# 20160428.net
KiCad netlist of a schematic drawn in Altium Designer
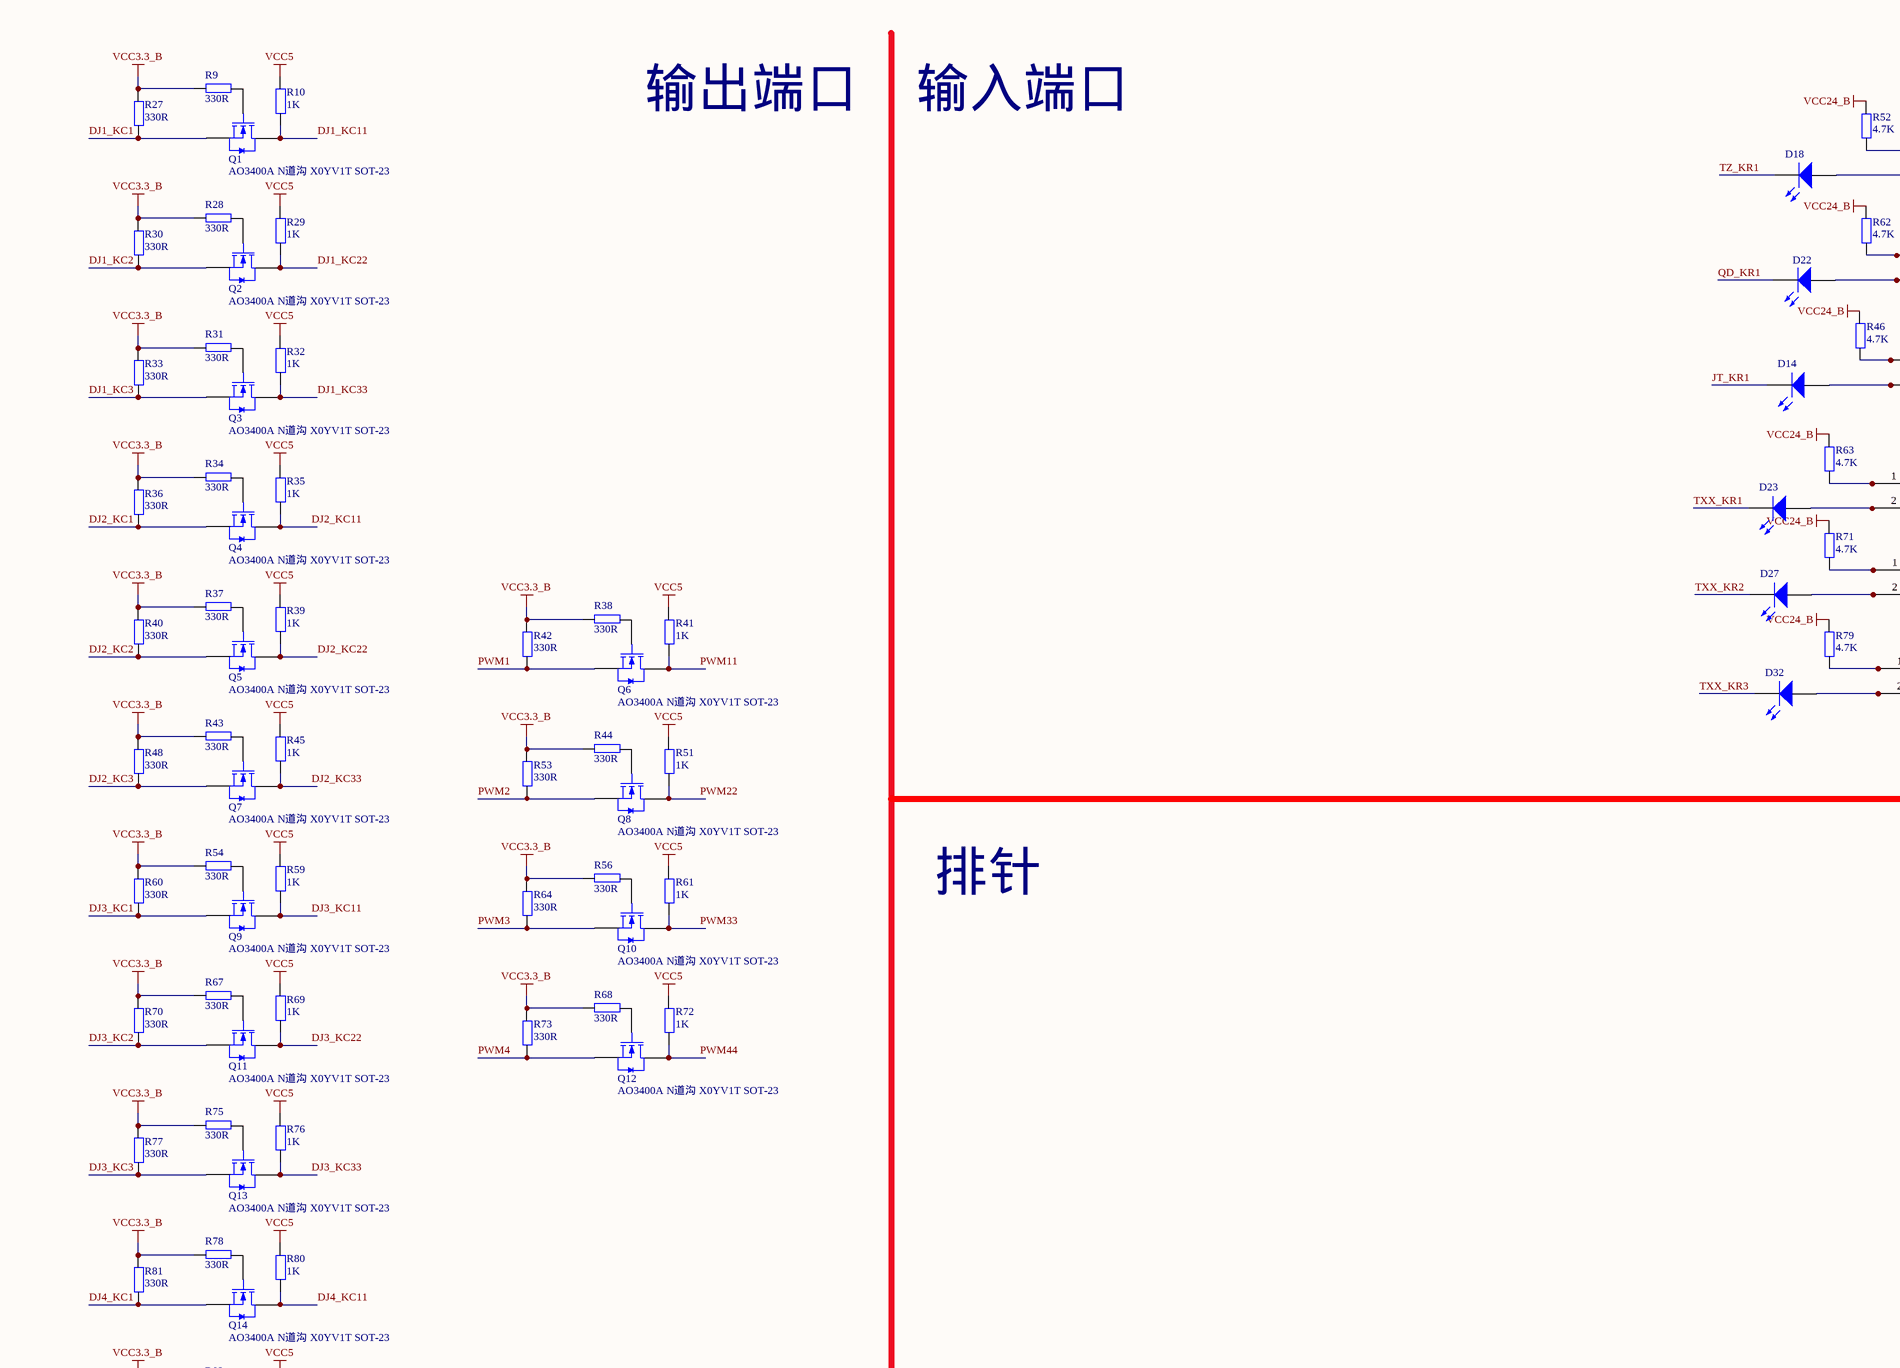
[diagram p0: 底板20160428.SchDoc, top left]
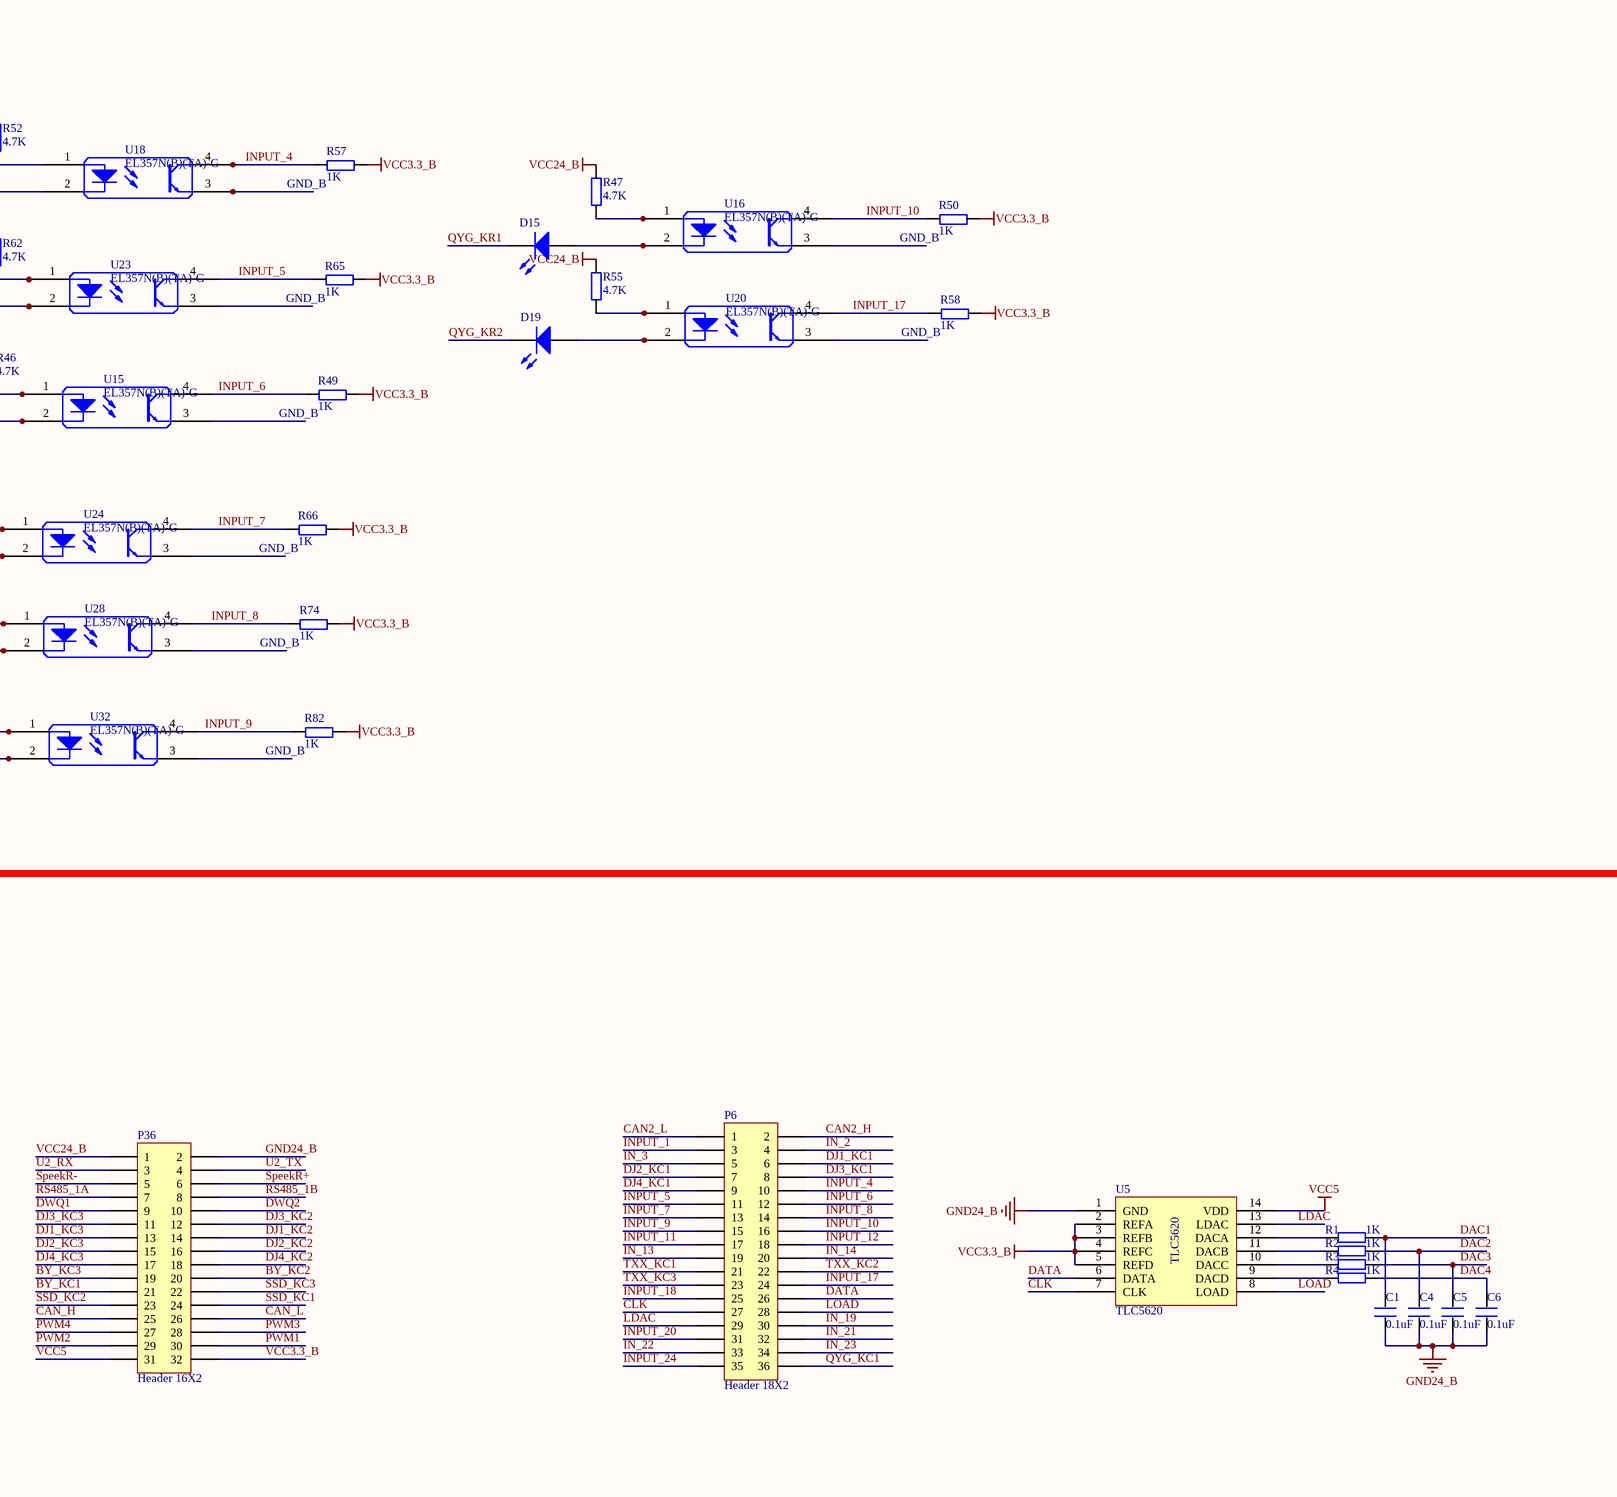
[diagram p1: 底板20160428.SchDoc, top right]
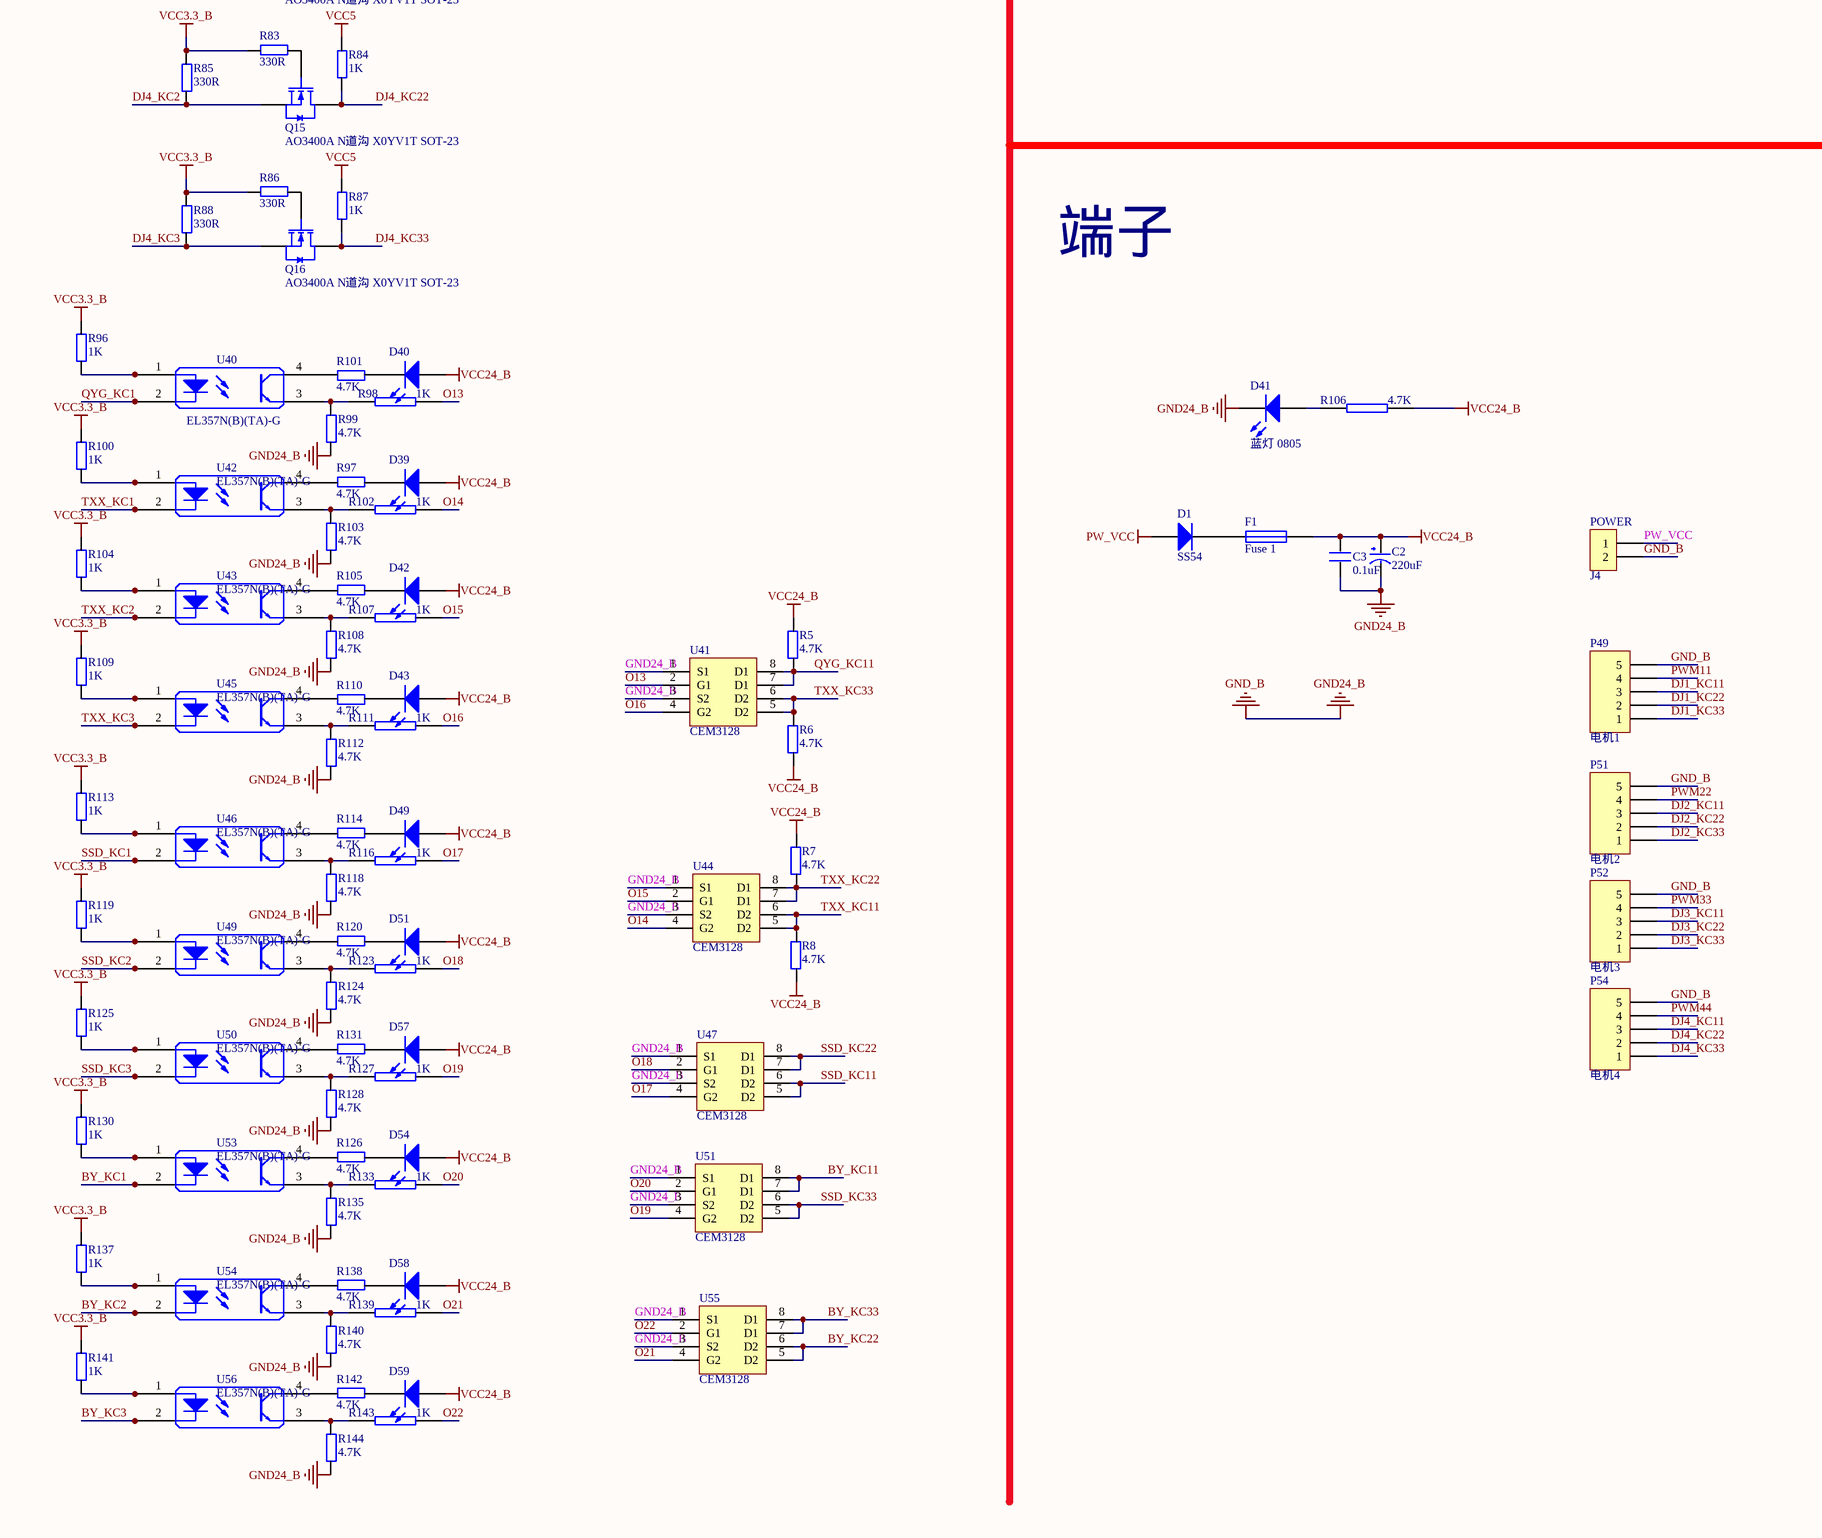
[diagram p2: 底板20160428.SchDoc, bottom left]
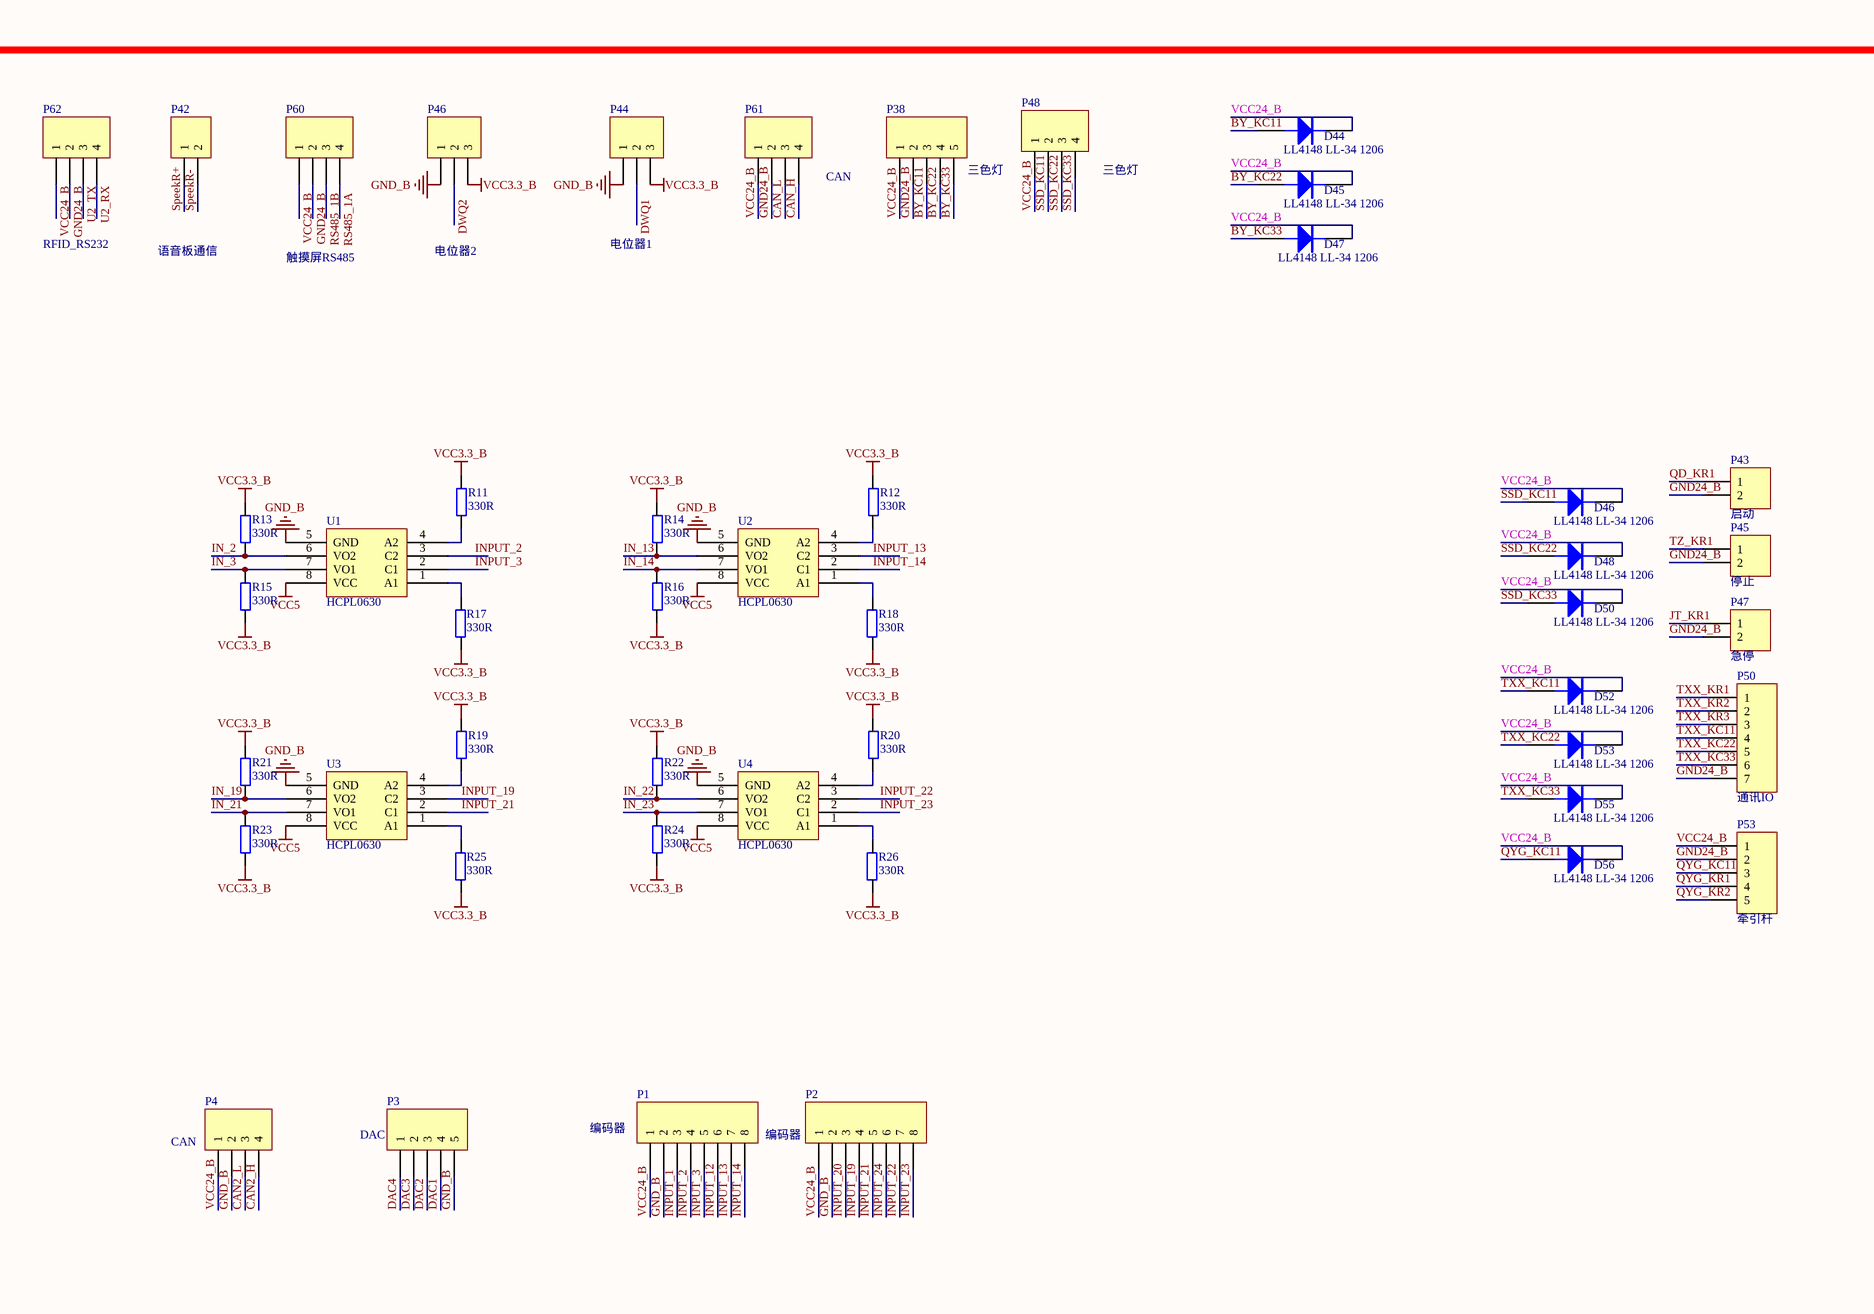
[diagram p3: 底板20160428.SchDoc, bottom right]

(export (version "E")
  (design (tool "Eeschema 10.0.6"))
  (components
    (comp (ref "C1") (value "0.1uF") (footprint "0603") (libsource (lib "WarShip V3_SCH") (part "C")))
    (comp (ref "C2") (value "220uF") (footprint "CC6.56.5") (libsource (lib "WarShip V3_SCH") (part "CAP")))
    (comp (ref "C3") (value "0.1uF") (footprint "0805") (libsource (lib "WarShip V3_SCH") (part "C")))
    (comp (ref "C4") (value "0.1uF") (footprint "0603") (libsource (lib "WarShip V3_SCH") (part "C")))
    (comp (ref "C5") (value "0.1uF") (footprint "0603") (libsource (lib "WarShip V3_SCH") (part "C")))
    (comp (ref "C6") (value "0.1uF") (footprint "0603") (libsource (lib "WarShip V3_SCH") (part "C")))
    (comp (ref "D1")
      (value "SS54")
      (footprint "SMA(DO-214AC)_S1")
      (description "二极管")
      (libsource (lib "Miscellaneous Devices LC") (part "SMA(DO-214AC) SS54"))
    )
    (comp (ref "D14")
      (value "红灯 0805")
      (footprint "LC-0805_LED_S1")
      (description "Typical INFRARED GaAs LED")
      (fields (field (name "PUBLISHER") "Altium Limited"))
      (libsource (lib "继电器板_1") (part "LED0"))
    )
    (comp (ref "D15")
      (value "红灯 0805")
      (footprint "LC-0805_LED_S1")
      (description "Typical INFRARED GaAs LED")
      (fields (field (name "PUBLISHER") "Altium Limited"))
      (libsource (lib "继电器板_1") (part "LED0"))
    )
    (comp (ref "D18")
      (value "红灯 0805")
      (footprint "LC-0805_LED_S1")
      (description "Typical INFRARED GaAs LED")
      (fields (field (name "PUBLISHER") "Altium Limited"))
      (libsource (lib "继电器板_1") (part "LED0"))
    )
    (comp (ref "D19")
      (value "红灯 0805")
      (footprint "LC-0805_LED_S1")
      (description "Typical INFRARED GaAs LED")
      (fields (field (name "PUBLISHER") "Altium Limited"))
      (libsource (lib "继电器板_1") (part "LED0"))
    )
    (comp (ref "D22")
      (value "红灯 0805")
      (footprint "LC-0805_LED_S1")
      (description "Typical INFRARED GaAs LED")
      (fields (field (name "PUBLISHER") "Altium Limited"))
      (libsource (lib "继电器板_1") (part "LED0"))
    )
    (comp (ref "D23")
      (value "红灯 0805")
      (footprint "LC-0805_LED_S1")
      (description "Typical INFRARED GaAs LED")
      (fields (field (name "PUBLISHER") "Altium Limited"))
      (libsource (lib "继电器板_1") (part "LED0"))
    )
    (comp (ref "D27")
      (value "红灯 0805")
      (footprint "LC-0805_LED_S1")
      (description "Typical INFRARED GaAs LED")
      (fields (field (name "PUBLISHER") "Altium Limited"))
      (libsource (lib "继电器板_1") (part "LED0"))
    )
    (comp (ref "D32")
      (value "红灯 0805")
      (footprint "LC-0805_LED_S1")
      (description "Typical INFRARED GaAs LED")
      (fields (field (name "PUBLISHER") "Altium Limited"))
      (libsource (lib "继电器板_1") (part "LED0"))
    )
    (comp (ref "D39")
      (value "红灯 0805")
      (footprint "LC-0805_LED_S1")
      (description "Typical INFRARED GaAs LED")
      (fields (field (name "PUBLISHER") "Altium Limited"))
      (libsource (lib "继电器板_1") (part "LED0"))
    )
    (comp (ref "D40")
      (value "红灯 0805")
      (footprint "LC-0805_LED_S1")
      (description "Typical INFRARED GaAs LED")
      (fields (field (name "PUBLISHER") "Altium Limited"))
      (libsource (lib "继电器板_1") (part "LED0"))
    )
    (comp (ref "D41")
      (value "蓝灯 0805")
      (footprint "0805_LED_S1")
      (description "发光二极管")
      (libsource (lib "Miscellaneous Devices LC - 副本") (part "0805 蓝灯"))
    )
    (comp (ref "D42")
      (value "红灯 0805")
      (footprint "LC-0805_LED_S1")
      (description "Typical INFRARED GaAs LED")
      (fields (field (name "PUBLISHER") "Altium Limited"))
      (libsource (lib "继电器板_1") (part "LED0"))
    )
    (comp (ref "D43")
      (value "红灯 0805")
      (footprint "LC-0805_LED_S1")
      (description "Typical INFRARED GaAs LED")
      (fields (field (name "PUBLISHER") "Altium Limited"))
      (libsource (lib "继电器板_1") (part "LED0"))
    )
    (comp (ref "D44")
      (value "LL4148 LL-34 1206")
      (footprint "LC-LL-34")
      (description "Diode")
      (libsource (lib "*") (part "DIODE"))
    )
    (comp (ref "D45")
      (value "LL4148 LL-34 1206")
      (footprint "LC-LL-34")
      (description "Diode")
      (libsource (lib "*") (part "DIODE"))
    )
    (comp (ref "D46")
      (value "LL4148 LL-34 1206")
      (footprint "LC-LL-34")
      (description "Diode")
      (libsource (lib "*") (part "DIODE"))
    )
    (comp (ref "D47")
      (value "LL4148 LL-34 1206")
      (footprint "LC-LL-34")
      (description "Diode")
      (libsource (lib "*") (part "DIODE"))
    )
    (comp (ref "D48")
      (value "LL4148 LL-34 1206")
      (footprint "LC-LL-34")
      (description "Diode")
      (libsource (lib "*") (part "DIODE"))
    )
    (comp (ref "D49")
      (value "红灯 0805")
      (footprint "LC-0805_LED_S1")
      (description "Typical INFRARED GaAs LED")
      (fields (field (name "PUBLISHER") "Altium Limited"))
      (libsource (lib "继电器板_1") (part "LED0"))
    )
    (comp (ref "D50")
      (value "LL4148 LL-34 1206")
      (footprint "LC-LL-34")
      (description "Diode")
      (libsource (lib "*") (part "DIODE"))
    )
    (comp (ref "D51")
      (value "红灯 0805")
      (footprint "LC-0805_LED_S1")
      (description "Typical INFRARED GaAs LED")
      (fields (field (name "PUBLISHER") "Altium Limited"))
      (libsource (lib "继电器板_1") (part "LED0"))
    )
    (comp (ref "D52")
      (value "LL4148 LL-34 1206")
      (footprint "LC-LL-34")
      (description "Diode")
      (libsource (lib "*") (part "DIODE"))
    )
    (comp (ref "D53")
      (value "LL4148 LL-34 1206")
      (footprint "LC-LL-34")
      (description "Diode")
      (libsource (lib "*") (part "DIODE"))
    )
    (comp (ref "D54")
      (value "红灯 0805")
      (footprint "LC-0805_LED_S1")
      (description "Typical INFRARED GaAs LED")
      (fields (field (name "PUBLISHER") "Altium Limited"))
      (libsource (lib "继电器板_1") (part "LED0"))
    )
    (comp (ref "D55")
      (value "LL4148 LL-34 1206")
      (footprint "LC-LL-34")
      (description "Diode")
      (libsource (lib "*") (part "DIODE"))
    )
    (comp (ref "D56")
      (value "LL4148 LL-34 1206")
      (footprint "LC-LL-34")
      (description "Diode")
      (libsource (lib "*") (part "DIODE"))
    )
    (comp (ref "D57")
      (value "红灯 0805")
      (footprint "LC-0805_LED_S1")
      (description "Typical INFRARED GaAs LED")
      (fields (field (name "PUBLISHER") "Altium Limited"))
      (libsource (lib "继电器板_1") (part "LED0"))
    )
    (comp (ref "D58")
      (value "红灯 0805")
      (footprint "LC-0805_LED_S1")
      (description "Typical INFRARED GaAs LED")
      (fields (field (name "PUBLISHER") "Altium Limited"))
      (libsource (lib "继电器板_1") (part "LED0"))
    )
    (comp (ref "D59")
      (value "红灯 0805")
      (footprint "LC-0805_LED_S1")
      (description "Typical INFRARED GaAs LED")
      (fields (field (name "PUBLISHER") "Altium Limited"))
      (libsource (lib "继电器板_1") (part "LED0"))
    )
    (comp (ref "F1")
      (value "Fuse 1")
      (footprint "1206")
      (description "Fuse")
      (fields (field (name "PUBLISHER") "Altium Limited"))
      (libsource (lib "Miscellaneous Devices") (part "Fuse 1"))
    )
    (comp (ref "J4")
      (value "CON2")
      (footprint "DZ-2-3.5")
      (description "Connector")
      (libsource (lib "*") (part "CON2"))
    )
    (comp (ref "P1")
      (value "编码器")
      (footprint "DZ-8-3.5")
      (description "Header, 8-Pin")
      (fields (field (name "PUBLISHER") "Altium Limited"))
      (libsource (lib "Miscellaneous Connectors") (part "Header 8"))
    )
    (comp (ref "P2")
      (value "编码器")
      (footprint "DZ-8-3.5")
      (description "Header, 8-Pin")
      (fields (field (name "PUBLISHER") "Altium Limited"))
      (libsource (lib "Miscellaneous Connectors") (part "Header 8"))
    )
    (comp (ref "P3")
      (value "DAC")
      (footprint "DZ-5-3.5")
      (description "Header, 5-Pin")
      (fields (field (name "PUBLISHER") "Altium Limited"))
      (libsource (lib "") (part "Header 5_2"))
    )
    (comp (ref "P4")
      (value "CAN")
      (footprint "DZ-4-3.5")
      (description "Header, 4-Pin")
      (fields (field (name "PUBLISHER") "Altium Limited"))
      (libsource (lib "Miscellaneous Connectors") (part "Header 4"))
    )
    (comp (ref "P6")
      (value "Header 18X2")
      (footprint "HDR2X18")
      (description "Header, 18-Pin, Dual row")
      (fields (field (name "PUBLISHER") "Altium Limited"))
      (libsource (lib "Miscellaneous Connectors") (part "Header 18X2"))
    )
    (comp (ref "P36")
      (value "Header 16X2")
      (footprint "HDR2X16")
      (description "Header, 16-Pin, Dual row")
      (fields (field (name "PUBLISHER") "Altium Limited"))
      (libsource (lib "Miscellaneous Connectors") (part "Header 16X2"))
    )
    (comp (ref "P38")
      (value "三色灯")
      (footprint "DZ-5-3.5")
      (description "Header, 5-Pin")
      (fields (field (name "PUBLISHER") "Altium Limited"))
      (libsource (lib "") (part "Header 5_2"))
    )
    (comp (ref "P42")
      (value "语音板通信")
      (footprint "DZ-2-3.5")
      (description "Header, 2-Pin")
      (fields (field (name "PUBLISHER") "Altium Limited"))
      (libsource (lib "Miscellaneous Connectors") (part "Header 2"))
    )
    (comp (ref "P43")
      (value "启动")
      (footprint "DZ-2-3.5")
      (description "Header, 2-Pin")
      (fields (field (name "PUBLISHER") "Altium Limited"))
      (libsource (lib "") (part "Header 2_1"))
    )
    (comp (ref "P44")
      (value "电位器1")
      (footprint "DZ-3-3.5")
      (description "Header, 3-Pin")
      (fields (field (name "PUBLISHER") "Altium Limited"))
      (libsource (lib "Miscellaneous Connectors") (part "Header 3"))
    )
    (comp (ref "P45")
      (value "停止")
      (footprint "DZ-2-3.5")
      (description "Header, 2-Pin")
      (fields (field (name "PUBLISHER") "Altium Limited"))
      (libsource (lib "") (part "Header 2_1"))
    )
    (comp (ref "P46")
      (value "电位器2")
      (footprint "DZ-3-3.5")
      (description "Header, 3-Pin")
      (fields (field (name "PUBLISHER") "Altium Limited"))
      (libsource (lib "Miscellaneous Connectors") (part "Header 3"))
    )
    (comp (ref "P47")
      (value "急停")
      (footprint "DZ-2-3.5")
      (description "Header, 2-Pin")
      (fields (field (name "PUBLISHER") "Altium Limited"))
      (libsource (lib "") (part "Header 2_1"))
    )
    (comp (ref "P48")
      (value "三色灯")
      (footprint "DZ-4-3.5")
      (description "Header, 4-Pin")
      (fields (field (name "PUBLISHER") "Altium Limited"))
      (libsource (lib "Miscellaneous Connectors") (part "Header 4"))
    )
    (comp (ref "P49")
      (value "电机1")
      (footprint "DZ-5-3.5")
      (description "Header, 5-Pin")
      (fields (field (name "PUBLISHER") "Altium Limited"))
      (libsource (lib "") (part "Header 5_1"))
    )
    (comp (ref "P50")
      (value "通讯IO")
      (footprint "DZ-7-3.5")
      (description "Header, 7-Pin")
      (fields (field (name "PUBLISHER") "Altium Limited"))
      (libsource (lib "Miscellaneous Connectors") (part "Header 7"))
    )
    (comp (ref "P51")
      (value "电机2")
      (footprint "DZ-5-3.5")
      (description "Header, 5-Pin")
      (fields (field (name "PUBLISHER") "Altium Limited"))
      (libsource (lib "") (part "Header 5_1"))
    )
    (comp (ref "P52")
      (value "电机3")
      (footprint "DZ-5-3.5")
      (description "Header, 5-Pin")
      (fields (field (name "PUBLISHER") "Altium Limited"))
      (libsource (lib "") (part "Header 5_1"))
    )
    (comp (ref "P53")
      (value "牵引杆")
      (footprint "DZ-5-3.5")
      (description "Header, 5-Pin")
      (fields (field (name "PUBLISHER") "Altium Limited"))
      (libsource (lib "Miscellaneous Connectors") (part "Header 5"))
    )
    (comp (ref "P54")
      (value "电机4")
      (footprint "DZ-5-3.5")
      (description "Header, 5-Pin")
      (fields (field (name "PUBLISHER") "Altium Limited"))
      (libsource (lib "") (part "Header 5_1"))
    )
    (comp (ref "P60")
      (value "触摸屏RS485")
      (footprint "DZ-4-3.5")
      (description "Header, 4-Pin")
      (fields (field (name "PUBLISHER") "Altium Limited"))
      (libsource (lib "Miscellaneous Connectors") (part "Header 4"))
    )
    (comp (ref "P61")
      (value "CAN")
      (footprint "DZ-4-3.5")
      (description "Header, 4-Pin")
      (fields (field (name "PUBLISHER") "Altium Limited"))
      (libsource (lib "Miscellaneous Connectors") (part "Header 4"))
    )
    (comp (ref "P62")
      (value "RFID_RS232")
      (footprint "DZ-4-3.5")
      (description "Header, 4-Pin")
      (fields (field (name "PUBLISHER") "Altium Limited"))
      (libsource (lib "Miscellaneous Connectors") (part "Header 4"))
    )
    (comp (ref "Q1")
      (value "AO3400A N道沟 X0YV1T SOT-23")
      (footprint "SOT-23-3L")
      (description "MOS(场效应管)")
      (libsource (lib "Miscellaneous Devices LC") (part "AO3400A N道沟 X0YV1T SOT-23"))
    )
    (comp (ref "Q2")
      (value "AO3400A N道沟 X0YV1T SOT-23")
      (footprint "SOT-23-3L")
      (description "MOS(场效应管)")
      (libsource (lib "Miscellaneous Devices LC") (part "AO3400A N道沟 X0YV1T SOT-23"))
    )
    (comp (ref "Q3")
      (value "AO3400A N道沟 X0YV1T SOT-23")
      (footprint "SOT-23-3L")
      (description "MOS(场效应管)")
      (libsource (lib "Miscellaneous Devices LC") (part "AO3400A N道沟 X0YV1T SOT-23"))
    )
    (comp (ref "Q4")
      (value "AO3400A N道沟 X0YV1T SOT-23")
      (footprint "SOT-23-3L")
      (description "MOS(场效应管)")
      (libsource (lib "Miscellaneous Devices LC") (part "AO3400A N道沟 X0YV1T SOT-23"))
    )
    (comp (ref "Q5")
      (value "AO3400A N道沟 X0YV1T SOT-23")
      (footprint "SOT-23-3L")
      (description "MOS(场效应管)")
      (libsource (lib "Miscellaneous Devices LC") (part "AO3400A N道沟 X0YV1T SOT-23"))
    )
    (comp (ref "Q6")
      (value "AO3400A N道沟 X0YV1T SOT-23")
      (footprint "SOT-23-3L")
      (description "MOS(场效应管)")
      (libsource (lib "Miscellaneous Devices LC") (part "AO3400A N道沟 X0YV1T SOT-23"))
    )
    (comp (ref "Q7")
      (value "AO3400A N道沟 X0YV1T SOT-23")
      (footprint "SOT-23-3L")
      (description "MOS(场效应管)")
      (libsource (lib "Miscellaneous Devices LC") (part "AO3400A N道沟 X0YV1T SOT-23"))
    )
    (comp (ref "Q8")
      (value "AO3400A N道沟 X0YV1T SOT-23")
      (footprint "SOT-23-3L")
      (description "MOS(场效应管)")
      (libsource (lib "Miscellaneous Devices LC") (part "AO3400A N道沟 X0YV1T SOT-23"))
    )
    (comp (ref "Q9")
      (value "AO3400A N道沟 X0YV1T SOT-23")
      (footprint "SOT-23-3L")
      (description "MOS(场效应管)")
      (libsource (lib "Miscellaneous Devices LC") (part "AO3400A N道沟 X0YV1T SOT-23"))
    )
    (comp (ref "Q10")
      (value "AO3400A N道沟 X0YV1T SOT-23")
      (footprint "SOT-23-3L")
      (description "MOS(场效应管)")
      (libsource (lib "Miscellaneous Devices LC") (part "AO3400A N道沟 X0YV1T SOT-23"))
    )
    (comp (ref "Q11")
      (value "AO3400A N道沟 X0YV1T SOT-23")
      (footprint "SOT-23-3L")
      (description "MOS(场效应管)")
      (libsource (lib "Miscellaneous Devices LC") (part "AO3400A N道沟 X0YV1T SOT-23"))
    )
    (comp (ref "Q12")
      (value "AO3400A N道沟 X0YV1T SOT-23")
      (footprint "SOT-23-3L")
      (description "MOS(场效应管)")
      (libsource (lib "Miscellaneous Devices LC") (part "AO3400A N道沟 X0YV1T SOT-23"))
    )
    (comp (ref "Q13")
      (value "AO3400A N道沟 X0YV1T SOT-23")
      (footprint "SOT-23-3L")
      (description "MOS(场效应管)")
      (libsource (lib "Miscellaneous Devices LC") (part "AO3400A N道沟 X0YV1T SOT-23"))
    )
    (comp (ref "Q14")
      (value "AO3400A N道沟 X0YV1T SOT-23")
      (footprint "SOT-23-3L")
      (description "MOS(场效应管)")
      (libsource (lib "Miscellaneous Devices LC") (part "AO3400A N道沟 X0YV1T SOT-23"))
    )
    (comp (ref "Q15")
      (value "AO3400A N道沟 X0YV1T SOT-23")
      (footprint "SOT-23-3L")
      (description "MOS(场效应管)")
      (libsource (lib "Miscellaneous Devices LC") (part "AO3400A N道沟 X0YV1T SOT-23"))
    )
    (comp (ref "Q16")
      (value "AO3400A N道沟 X0YV1T SOT-23")
      (footprint "SOT-23-3L")
      (description "MOS(场效应管)")
      (libsource (lib "Miscellaneous Devices LC") (part "AO3400A N道沟 X0YV1T SOT-23"))
    )
    (comp (ref "R1") (value "1K") (footprint "0603") (libsource (lib "Explorer STM32F407封装库") (part "R_2")))
    (comp (ref "R2") (value "1K") (footprint "0603") (libsource (lib "Explorer STM32F407封装库") (part "R_2")))
    (comp (ref "R3") (value "1K") (footprint "0603") (libsource (lib "Explorer STM32F407封装库") (part "R_2")))
    (comp (ref "R4") (value "1K") (footprint "0603") (libsource (lib "Explorer STM32F407封装库") (part "R_2")))
    (comp (ref "R5") (value "4.7K") (footprint "0603") (libsource (lib "Explorer STM32F407封装库") (part "R_2")))
    (comp (ref "R6") (value "4.7K") (footprint "0603") (libsource (lib "Explorer STM32F407封装库") (part "R_2")))
    (comp (ref "R7") (value "4.7K") (footprint "0603") (libsource (lib "Explorer STM32F407封装库") (part "R_2")))
    (comp (ref "R8") (value "4.7K") (footprint "0603") (libsource (lib "Explorer STM32F407封装库") (part "R_2")))
    (comp (ref "R9") (value "330R") (footprint "0603") (libsource (lib "Explorer STM32F407封装库") (part "R_2")))
    (comp (ref "R10") (value "1K") (footprint "0603") (libsource (lib "Explorer STM32F407封装库") (part "R_2")))
    (comp (ref "R11")
      (value "330R")
      (footprint "0603")
      (libsource (lib "Explorer STM32F407封装库") (part "R_2"))
    )
    (comp (ref "R12")
      (value "330R")
      (footprint "0603")
      (libsource (lib "Explorer STM32F407封装库") (part "R_2"))
    )
    (comp (ref "R13")
      (value "330R")
      (footprint "0603")
      (libsource (lib "Explorer STM32F407封装库") (part "R_2"))
    )
    (comp (ref "R14")
      (value "330R")
      (footprint "0603")
      (libsource (lib "Explorer STM32F407封装库") (part "R_2"))
    )
    (comp (ref "R15")
      (value "330R")
      (footprint "0603")
      (libsource (lib "Explorer STM32F407封装库") (part "R_2"))
    )
    (comp (ref "R16")
      (value "330R")
      (footprint "0603")
      (libsource (lib "Explorer STM32F407封装库") (part "R_2"))
    )
    (comp (ref "R17")
      (value "330R")
      (footprint "0603")
      (libsource (lib "Explorer STM32F407封装库") (part "R_2"))
    )
    (comp (ref "R18")
      (value "330R")
      (footprint "0603")
      (libsource (lib "Explorer STM32F407封装库") (part "R_2"))
    )
    (comp (ref "R19")
      (value "330R")
      (footprint "0603")
      (libsource (lib "Explorer STM32F407封装库") (part "R_2"))
    )
    (comp (ref "R20")
      (value "330R")
      (footprint "0603")
      (libsource (lib "Explorer STM32F407封装库") (part "R_2"))
    )
    (comp (ref "R21")
      (value "330R")
      (footprint "0603")
      (libsource (lib "Explorer STM32F407封装库") (part "R_2"))
    )
    (comp (ref "R22")
      (value "330R")
      (footprint "0603")
      (libsource (lib "Explorer STM32F407封装库") (part "R_2"))
    )
    (comp (ref "R23")
      (value "330R")
      (footprint "0603")
      (libsource (lib "Explorer STM32F407封装库") (part "R_2"))
    )
    (comp (ref "R24")
      (value "330R")
      (footprint "0603")
      (libsource (lib "Explorer STM32F407封装库") (part "R_2"))
    )
    (comp (ref "R25")
      (value "330R")
      (footprint "0603")
      (libsource (lib "Explorer STM32F407封装库") (part "R_2"))
    )
    (comp (ref "R26")
      (value "330R")
      (footprint "0603")
      (libsource (lib "Explorer STM32F407封装库") (part "R_2"))
    )
    (comp (ref "R27")
      (value "330R")
      (footprint "0603")
      (libsource (lib "Explorer STM32F407封装库") (part "R_2"))
    )
    (comp (ref "R28")
      (value "330R")
      (footprint "0603")
      (libsource (lib "Explorer STM32F407封装库") (part "R_2"))
    )
    (comp (ref "R29") (value "1K") (footprint "0603") (libsource (lib "Explorer STM32F407封装库") (part "R_2")))
    (comp (ref "R30")
      (value "330R")
      (footprint "0603")
      (libsource (lib "Explorer STM32F407封装库") (part "R_2"))
    )
    (comp (ref "R31")
      (value "330R")
      (footprint "0603")
      (libsource (lib "Explorer STM32F407封装库") (part "R_2"))
    )
    (comp (ref "R32") (value "1K") (footprint "0603") (libsource (lib "Explorer STM32F407封装库") (part "R_2")))
    (comp (ref "R33")
      (value "330R")
      (footprint "0603")
      (libsource (lib "Explorer STM32F407封装库") (part "R_2"))
    )
    (comp (ref "R34")
      (value "330R")
      (footprint "0603")
      (libsource (lib "Explorer STM32F407封装库") (part "R_2"))
    )
    (comp (ref "R35") (value "1K") (footprint "0603") (libsource (lib "Explorer STM32F407封装库") (part "R_2")))
    (comp (ref "R36")
      (value "330R")
      (footprint "0603")
      (libsource (lib "Explorer STM32F407封装库") (part "R_2"))
    )
    (comp (ref "R37")
      (value "330R")
      (footprint "0603")
      (libsource (lib "Explorer STM32F407封装库") (part "R_2"))
    )
    (comp (ref "R38")
      (value "330R")
      (footprint "0603")
      (libsource (lib "Explorer STM32F407封装库") (part "R_2"))
    )
    (comp (ref "R39") (value "1K") (footprint "0603") (libsource (lib "Explorer STM32F407封装库") (part "R_2")))
    (comp (ref "R40")
      (value "330R")
      (footprint "0603")
      (libsource (lib "Explorer STM32F407封装库") (part "R_2"))
    )
    (comp (ref "R41") (value "1K") (footprint "0603") (libsource (lib "Explorer STM32F407封装库") (part "R_2")))
    (comp (ref "R42")
      (value "330R")
      (footprint "0603")
      (libsource (lib "Explorer STM32F407封装库") (part "R_2"))
    )
    (comp (ref "R43")
      (value "330R")
      (footprint "0603")
      (libsource (lib "Explorer STM32F407封装库") (part "R_2"))
    )
    (comp (ref "R44")
      (value "330R")
      (footprint "0603")
      (libsource (lib "Explorer STM32F407封装库") (part "R_2"))
    )
    (comp (ref "R45") (value "1K") (footprint "0603") (libsource (lib "Explorer STM32F407封装库") (part "R_2")))
    (comp (ref "R46")
      (value "4.7K")
      (footprint "0603")
      (libsource (lib "Explorer STM32F407封装库") (part "R_2"))
    )
    (comp (ref "R47")
      (value "4.7K")
      (footprint "0603")
      (libsource (lib "Explorer STM32F407封装库") (part "R_2"))
    )
    (comp (ref "R48")
      (value "330R")
      (footprint "0603")
      (libsource (lib "Explorer STM32F407封装库") (part "R_2"))
    )
    (comp (ref "R49") (value "1K") (footprint "0603") (libsource (lib "Explorer STM32F407封装库") (part "R_2")))
    (comp (ref "R50") (value "1K") (footprint "0603") (libsource (lib "Explorer STM32F407封装库") (part "R_2")))
    (comp (ref "R51") (value "1K") (footprint "0603") (libsource (lib "Explorer STM32F407封装库") (part "R_2")))
    (comp (ref "R52")
      (value "4.7K")
      (footprint "0603")
      (libsource (lib "Explorer STM32F407封装库") (part "R_2"))
    )
    (comp (ref "R53")
      (value "330R")
      (footprint "0603")
      (libsource (lib "Explorer STM32F407封装库") (part "R_2"))
    )
    (comp (ref "R54")
      (value "330R")
      (footprint "0603")
      (libsource (lib "Explorer STM32F407封装库") (part "R_2"))
    )
    (comp (ref "R55")
      (value "4.7K")
      (footprint "0603")
      (libsource (lib "Explorer STM32F407封装库") (part "R_2"))
    )
    (comp (ref "R56")
      (value "330R")
      (footprint "0603")
      (libsource (lib "Explorer STM32F407封装库") (part "R_2"))
    )
    (comp (ref "R57") (value "1K") (footprint "0603") (libsource (lib "Explorer STM32F407封装库") (part "R_2")))
    (comp (ref "R58") (value "1K") (footprint "0603") (libsource (lib "Explorer STM32F407封装库") (part "R_2")))
    (comp (ref "R59") (value "1K") (footprint "0603") (libsource (lib "Explorer STM32F407封装库") (part "R_2")))
    (comp (ref "R60")
      (value "330R")
      (footprint "0603")
      (libsource (lib "Explorer STM32F407封装库") (part "R_2"))
    )
    (comp (ref "R61") (value "1K") (footprint "0603") (libsource (lib "Explorer STM32F407封装库") (part "R_2")))
    (comp (ref "R62")
      (value "4.7K")
      (footprint "0603")
      (libsource (lib "Explorer STM32F407封装库") (part "R_2"))
    )
    (comp (ref "R63")
      (value "4.7K")
      (footprint "0603")
      (libsource (lib "Explorer STM32F407封装库") (part "R_2"))
    )
    (comp (ref "R64")
      (value "330R")
      (footprint "0603")
      (libsource (lib "Explorer STM32F407封装库") (part "R_2"))
    )
    (comp (ref "R65") (value "1K") (footprint "0603") (libsource (lib "Explorer STM32F407封装库") (part "R_2")))
    (comp (ref "R66") (value "1K") (footprint "0603") (libsource (lib "Explorer STM32F407封装库") (part "R_2")))
    (comp (ref "R67")
      (value "330R")
      (footprint "0603")
      (libsource (lib "Explorer STM32F407封装库") (part "R_2"))
    )
    (comp (ref "R68")
      (value "330R")
      (footprint "0603")
      (libsource (lib "Explorer STM32F407封装库") (part "R_2"))
    )
    (comp (ref "R69") (value "1K") (footprint "0603") (libsource (lib "Explorer STM32F407封装库") (part "R_2")))
    (comp (ref "R70")
      (value "330R")
      (footprint "0603")
      (libsource (lib "Explorer STM32F407封装库") (part "R_2"))
    )
    (comp (ref "R71")
      (value "4.7K")
      (footprint "0603")
      (libsource (lib "Explorer STM32F407封装库") (part "R_2"))
    )
    (comp (ref "R72") (value "1K") (footprint "0603") (libsource (lib "Explorer STM32F407封装库") (part "R_2")))
    (comp (ref "R73")
      (value "330R")
      (footprint "0603")
      (libsource (lib "Explorer STM32F407封装库") (part "R_2"))
    )
    (comp (ref "R74") (value "1K") (footprint "0603") (libsource (lib "Explorer STM32F407封装库") (part "R_2")))
    (comp (ref "R75")
      (value "330R")
      (footprint "0603")
      (libsource (lib "Explorer STM32F407封装库") (part "R_2"))
    )
    (comp (ref "R76") (value "1K") (footprint "0603") (libsource (lib "Explorer STM32F407封装库") (part "R_2")))
    (comp (ref "R77")
      (value "330R")
      (footprint "0603")
      (libsource (lib "Explorer STM32F407封装库") (part "R_2"))
    )
    (comp (ref "R78")
      (value "330R")
      (footprint "0603")
      (libsource (lib "Explorer STM32F407封装库") (part "R_2"))
    )
    (comp (ref "R79")
      (value "4.7K")
      (footprint "0603")
      (libsource (lib "Explorer STM32F407封装库") (part "R_2"))
    )
    (comp (ref "R80") (value "1K") (footprint "0603") (libsource (lib "Explorer STM32F407封装库") (part "R_2")))
    (comp (ref "R81")
      (value "330R")
      (footprint "0603")
      (libsource (lib "Explorer STM32F407封装库") (part "R_2"))
    )
    (comp (ref "R82") (value "1K") (footprint "0603") (libsource (lib "Explorer STM32F407封装库") (part "R_2")))
    (comp (ref "R83")
      (value "330R")
      (footprint "0603")
      (libsource (lib "Explorer STM32F407封装库") (part "R_2"))
    )
    (comp (ref "R84") (value "1K") (footprint "0603") (libsource (lib "Explorer STM32F407封装库") (part "R_2")))
    (comp (ref "R85")
      (value "330R")
      (footprint "0603")
      (libsource (lib "Explorer STM32F407封装库") (part "R_2"))
    )
    (comp (ref "R86")
      (value "330R")
      (footprint "0603")
      (libsource (lib "Explorer STM32F407封装库") (part "R_2"))
    )
    (comp (ref "R87") (value "1K") (footprint "0603") (libsource (lib "Explorer STM32F407封装库") (part "R_2")))
    (comp (ref "R88")
      (value "330R")
      (footprint "0603")
      (libsource (lib "Explorer STM32F407封装库") (part "R_2"))
    )
    (comp (ref "R96") (value "1K") (footprint "0603") (libsource (lib "Explorer STM32F407封装库") (part "R_2")))
    (comp (ref "R97")
      (value "4.7K")
      (footprint "0603")
      (libsource (lib "Explorer STM32F407封装库") (part "R_2"))
    )
    (comp (ref "R98") (value "1K") (footprint "0603") (libsource (lib "*") (part "RES2")))
    (comp (ref "R99")
      (value "4.7K")
      (footprint "0603")
      (libsource (lib "Explorer STM32F407封装库") (part "R_2"))
    )
    (comp (ref "R100") (value "1K") (footprint "0603") (libsource (lib "Explorer STM32F407封装库") (part "R_2")))
    (comp (ref "R101")
      (value "4.7K")
      (footprint "0603")
      (libsource (lib "Explorer STM32F407封装库") (part "R_2"))
    )
    (comp (ref "R102") (value "1K") (footprint "0603") (libsource (lib "*") (part "RES2")))
    (comp (ref "R103")
      (value "4.7K")
      (footprint "0603")
      (libsource (lib "Explorer STM32F407封装库") (part "R_2"))
    )
    (comp (ref "R104") (value "1K") (footprint "0603") (libsource (lib "Explorer STM32F407封装库") (part "R_2")))
    (comp (ref "R105")
      (value "4.7K")
      (footprint "0603")
      (libsource (lib "Explorer STM32F407封装库") (part "R_2"))
    )
    (comp (ref "R106") (value "4.7K") (footprint "0603") (libsource (lib "*") (part "RES2")))
    (comp (ref "R107") (value "1K") (footprint "0603") (libsource (lib "*") (part "RES2")))
    (comp (ref "R108")
      (value "4.7K")
      (footprint "0603")
      (libsource (lib "Explorer STM32F407封装库") (part "R_2"))
    )
    (comp (ref "R109") (value "1K") (footprint "0603") (libsource (lib "Explorer STM32F407封装库") (part "R_2")))
    (comp (ref "R110")
      (value "4.7K")
      (footprint "0603")
      (libsource (lib "Explorer STM32F407封装库") (part "R_2"))
    )
    (comp (ref "R111") (value "1K") (footprint "0603") (libsource (lib "*") (part "RES2")))
    (comp (ref "R112")
      (value "4.7K")
      (footprint "0603")
      (libsource (lib "Explorer STM32F407封装库") (part "R_2"))
    )
    (comp (ref "R113") (value "1K") (footprint "0603") (libsource (lib "Explorer STM32F407封装库") (part "R_2")))
    (comp (ref "R114")
      (value "4.7K")
      (footprint "0603")
      (libsource (lib "Explorer STM32F407封装库") (part "R_2"))
    )
    (comp (ref "R116") (value "1K") (footprint "0603") (libsource (lib "*") (part "RES2")))
    (comp (ref "R118")
      (value "4.7K")
      (footprint "0603")
      (libsource (lib "Explorer STM32F407封装库") (part "R_2"))
    )
    (comp (ref "R119") (value "1K") (footprint "0603") (libsource (lib "Explorer STM32F407封装库") (part "R_2")))
    (comp (ref "R120")
      (value "4.7K")
      (footprint "0603")
      (libsource (lib "Explorer STM32F407封装库") (part "R_2"))
    )
    (comp (ref "R123") (value "1K") (footprint "0603") (libsource (lib "*") (part "RES2")))
    (comp (ref "R124")
      (value "4.7K")
      (footprint "0603")
      (libsource (lib "Explorer STM32F407封装库") (part "R_2"))
    )
    (comp (ref "R125") (value "1K") (footprint "0603") (libsource (lib "Explorer STM32F407封装库") (part "R_2")))
    (comp (ref "R126")
      (value "4.7K")
      (footprint "0603")
      (libsource (lib "Explorer STM32F407封装库") (part "R_2"))
    )
    (comp (ref "R127") (value "1K") (footprint "0603") (libsource (lib "*") (part "RES2")))
    (comp (ref "R128")
      (value "4.7K")
      (footprint "0603")
      (libsource (lib "Explorer STM32F407封装库") (part "R_2"))
    )
    (comp (ref "R130") (value "1K") (footprint "0603") (libsource (lib "Explorer STM32F407封装库") (part "R_2")))
    (comp (ref "R131")
      (value "4.7K")
      (footprint "0603")
      (libsource (lib "Explorer STM32F407封装库") (part "R_2"))
    )
    (comp (ref "R133") (value "1K") (footprint "0603") (libsource (lib "*") (part "RES2")))
    (comp (ref "R135")
      (value "4.7K")
      (footprint "0603")
      (libsource (lib "Explorer STM32F407封装库") (part "R_2"))
    )
    (comp (ref "R137") (value "1K") (footprint "0603") (libsource (lib "Explorer STM32F407封装库") (part "R_2")))
    (comp (ref "R138")
      (value "4.7K")
      (footprint "0603")
      (libsource (lib "Explorer STM32F407封装库") (part "R_2"))
    )
    (comp (ref "R139") (value "1K") (footprint "0603") (libsource (lib "*") (part "RES2")))
    (comp (ref "R140")
      (value "4.7K")
      (footprint "0603")
      (libsource (lib "Explorer STM32F407封装库") (part "R_2"))
    )
    (comp (ref "R141") (value "1K") (footprint "0603") (libsource (lib "Explorer STM32F407封装库") (part "R_2")))
    (comp (ref "R142")
      (value "4.7K")
      (footprint "0603")
      (libsource (lib "Explorer STM32F407封装库") (part "R_2"))
    )
    (comp (ref "R143") (value "1K") (footprint "0603") (libsource (lib "*") (part "RES2")))
    (comp (ref "R144")
      (value "4.7K")
      (footprint "0603")
      (libsource (lib "Explorer STM32F407封装库") (part "R_2"))
    )
    (comp (ref "U1") (value "HCPL0630") (footprint "SO-8") (libsource (lib "EXPLORER") (part "HCPL0630")))
    (comp (ref "U2") (value "HCPL0630") (footprint "SO-8") (libsource (lib "EXPLORER") (part "HCPL0630")))
    (comp (ref "U3") (value "HCPL0630") (footprint "SO-8") (libsource (lib "EXPLORER") (part "HCPL0630")))
    (comp (ref "U4") (value "HCPL0630") (footprint "SO-8") (libsource (lib "EXPLORER") (part "HCPL0630")))
    (comp (ref "U5")
      (value "TLC5620")
      (footprint "LC-SOIC-14_150mil")
      (libsource (lib "Schlib1") (part "Component_1"))
    )
    (comp (ref "U15")
      (value "EL357N(B)(TA)-G")
      (footprint "LC-SOP-4_P2.54")
      (libsource (lib "*") (part "2701"))
    )
    (comp (ref "U16")
      (value "EL357N(B)(TA)-G")
      (footprint "LC-SOP-4_P2.54")
      (libsource (lib "*") (part "2701"))
    )
    (comp (ref "U18")
      (value "EL357N(B)(TA)-G")
      (footprint "LC-SOP-4_P2.54")
      (libsource (lib "*") (part "2701"))
    )
    (comp (ref "U20")
      (value "EL357N(B)(TA)-G")
      (footprint "LC-SOP-4_P2.54")
      (libsource (lib "*") (part "2701"))
    )
    (comp (ref "U23")
      (value "EL357N(B)(TA)-G")
      (footprint "LC-SOP-4_P2.54")
      (libsource (lib "*") (part "2701"))
    )
    (comp (ref "U24")
      (value "EL357N(B)(TA)-G")
      (footprint "LC-SOP-4_P2.54")
      (libsource (lib "*") (part "2701"))
    )
    (comp (ref "U28")
      (value "EL357N(B)(TA)-G")
      (footprint "LC-SOP-4_P2.54")
      (libsource (lib "*") (part "2701"))
    )
    (comp (ref "U32")
      (value "EL357N(B)(TA)-G")
      (footprint "LC-SOP-4_P2.54")
      (libsource (lib "*") (part "2701"))
    )
    (comp (ref "U40")
      (value "EL357N(B)(TA)-G")
      (footprint "LC-SOP-4_P2.54")
      (libsource (lib "*") (part "2701"))
    )
    (comp (ref "U41") (value "CEM3128") (footprint "SO-8") (libsource (lib "*") (part "AF4920N")))
    (comp (ref "U42")
      (value "EL357N(B)(TA)-G")
      (footprint "LC-SOP-4_P2.54")
      (libsource (lib "*") (part "2701"))
    )
    (comp (ref "U43")
      (value "EL357N(B)(TA)-G")
      (footprint "LC-SOP-4_P2.54")
      (libsource (lib "*") (part "2701"))
    )
    (comp (ref "U44") (value "CEM3128") (footprint "SO-8") (libsource (lib "*") (part "AF4920N")))
    (comp (ref "U45")
      (value "EL357N(B)(TA)-G")
      (footprint "LC-SOP-4_P2.54")
      (libsource (lib "*") (part "2701"))
    )
    (comp (ref "U46")
      (value "EL357N(B)(TA)-G")
      (footprint "LC-SOP-4_P2.54")
      (libsource (lib "*") (part "2701"))
    )
    (comp (ref "U47") (value "CEM3128") (footprint "SO-8") (libsource (lib "*") (part "AF4920N")))
    (comp (ref "U49")
      (value "EL357N(B)(TA)-G")
      (footprint "LC-SOP-4_P2.54")
      (libsource (lib "*") (part "2701"))
    )
    (comp (ref "U50")
      (value "EL357N(B)(TA)-G")
      (footprint "LC-SOP-4_P2.54")
      (libsource (lib "*") (part "2701"))
    )
    (comp (ref "U51") (value "CEM3128") (footprint "SO-8") (libsource (lib "*") (part "AF4920N")))
    (comp (ref "U53")
      (value "EL357N(B)(TA)-G")
      (footprint "LC-SOP-4_P2.54")
      (libsource (lib "*") (part "2701"))
    )
    (comp (ref "U54")
      (value "EL357N(B)(TA)-G")
      (footprint "LC-SOP-4_P2.54")
      (libsource (lib "*") (part "2701"))
    )
    (comp (ref "U55") (value "CEM3128") (footprint "SO-8") (libsource (lib "*") (part "AF4920N")))
    (comp (ref "U56")
      (value "EL357N(B)(TA)-G")
      (footprint "LC-SOP-4_P2.54")
      (libsource (lib "*") (part "2701"))
    )
  )
  (nets
    (net (code "1") (name "/BY_KC1") (class "Default")
      (node (ref "P36") (pin "21") (pinfunction "21_21") (pintype "passive"))
      (node (ref "U53") (pin "2") (pintype "passive"))
    )
    (net (code "2") (name "/BY_KC2") (class "Default")
      (node (ref "P36") (pin "20") (pinfunction "20_20") (pintype "passive"))
      (node (ref "U54") (pin "2") (pintype "passive"))
    )
    (net (code "3") (name "/BY_KC3") (class "Default")
      (node (ref "P36") (pin "19") (pinfunction "19_19") (pintype "passive"))
      (node (ref "U56") (pin "2") (pintype "passive"))
    )
    (net (code "4") (name "/BY_KC11") (class "Default")
      (node (ref "D44") (pin "1") (pinfunction "A_1") (pintype "passive"))
      (node (ref "P38") (pin "3") (pinfunction "3_3") (pintype "passive"))
      (node (ref "U51") (pin "7") (pinfunction "D1_7") (pintype "passive"))
      (node (ref "U51") (pin "8") (pinfunction "D1_8") (pintype "passive"))
    )
    (net (code "5") (name "/BY_KC22") (class "Default")
      (node (ref "D45") (pin "1") (pinfunction "A_1") (pintype "passive"))
      (node (ref "P38") (pin "4") (pinfunction "4_4") (pintype "passive"))
      (node (ref "U55") (pin "5") (pinfunction "D2_5") (pintype "passive"))
      (node (ref "U55") (pin "6") (pinfunction "D2_6") (pintype "passive"))
    )
    (net (code "6") (name "/BY_KC33") (class "Default")
      (node (ref "D47") (pin "1") (pinfunction "A_1") (pintype "passive"))
      (node (ref "P38") (pin "5") (pinfunction "5_5") (pintype "passive"))
      (node (ref "U55") (pin "7") (pinfunction "D1_7") (pintype "passive"))
      (node (ref "U55") (pin "8") (pinfunction "D1_8") (pintype "passive"))
    )
    (net (code "7") (name "/CAN2_H") (class "Default")
      (node (ref "P4") (pin "4") (pinfunction "4_4") (pintype "passive"))
      (node (ref "P6") (pin "2") (pinfunction "2_2") (pintype "passive"))
    )
    (net (code "8") (name "/CAN2_L") (class "Default")
      (node (ref "P4") (pin "3") (pinfunction "3_3") (pintype "passive"))
      (node (ref "P6") (pin "1") (pinfunction "1_1") (pintype "passive"))
    )
    (net (code "9") (name "/CAN_H") (class "Default")
      (node (ref "P36") (pin "25") (pinfunction "25_25") (pintype "passive"))
      (node (ref "P61") (pin "4") (pinfunction "4_4") (pintype "passive"))
    )
    (net (code "10") (name "/CAN_L") (class "Default")
      (node (ref "P36") (pin "26") (pinfunction "26_26") (pintype "passive"))
      (node (ref "P61") (pin "3") (pinfunction "3_3") (pintype "passive"))
    )
    (net (code "11") (name "/CLK") (class "Default")
      (node (ref "P6") (pin "27") (pinfunction "27_27") (pintype "passive"))
      (node (ref "U5") (pin "7") (pinfunction "CLK_7") (pintype "passive"))
    )
    (net (code "12") (name "/DAC1") (class "Default")
      (node (ref "C1") (pin "2") (pintype "passive"))
      (node (ref "P3") (pin "4") (pinfunction "4_4") (pintype "passive"))
      (node (ref "R1") (pin "1") (pintype "passive"))
    )
    (net (code "13") (name "/DAC2") (class "Default")
      (node (ref "C4") (pin "2") (pintype "passive"))
      (node (ref "P3") (pin "3") (pinfunction "3_3") (pintype "passive"))
      (node (ref "R2") (pin "1") (pintype "passive"))
    )
    (net (code "14") (name "/DAC3") (class "Default")
      (node (ref "C5") (pin "2") (pintype "passive"))
      (node (ref "P3") (pin "2") (pinfunction "2_2") (pintype "passive"))
      (node (ref "R3") (pin "1") (pintype "passive"))
    )
    (net (code "15") (name "/DAC4") (class "Default")
      (node (ref "C6") (pin "2") (pintype "passive"))
      (node (ref "P3") (pin "1") (pinfunction "1_1") (pintype "passive"))
      (node (ref "R4") (pin "1") (pintype "passive"))
    )
    (net (code "16") (name "/DATA") (class "Default")
      (node (ref "P6") (pin "26") (pinfunction "26_26") (pintype "passive"))
      (node (ref "U5") (pin "6") (pinfunction "DATA_6") (pintype "passive"))
    )
    (net (code "17") (name "/DJ1_KC1") (class "Default")
      (node (ref "P6") (pin "6") (pinfunction "6_6") (pintype "passive"))
      (node (ref "Q1") (pin "2") (pinfunction "S_2") (pintype "passive"))
      (node (ref "R27") (pin "1") (pintype "passive"))
    )
    (net (code "18") (name "/DJ1_KC2") (class "Default")
      (node (ref "P36") (pin "14") (pinfunction "14_14") (pintype "passive"))
      (node (ref "Q2") (pin "2") (pinfunction "S_2") (pintype "passive"))
      (node (ref "R30") (pin "1") (pintype "passive"))
    )
    (net (code "19") (name "/DJ1_KC3") (class "Default")
      (node (ref "P36") (pin "13") (pinfunction "13_13") (pintype "passive"))
      (node (ref "Q3") (pin "2") (pinfunction "S_2") (pintype "passive"))
      (node (ref "R33") (pin "1") (pintype "passive"))
    )
    (net (code "20") (name "/DJ1_KC11") (class "Default")
      (node (ref "P49") (pin "3") (pinfunction "3_3") (pintype "passive"))
      (node (ref "Q1") (pin "3") (pinfunction "D_3") (pintype "passive"))
      (node (ref "R10") (pin "1") (pintype "passive"))
    )
    (net (code "21") (name "/DJ1_KC22") (class "Default")
      (node (ref "P49") (pin "2") (pinfunction "2_2") (pintype "passive"))
      (node (ref "Q2") (pin "3") (pinfunction "D_3") (pintype "passive"))
      (node (ref "R29") (pin "1") (pintype "passive"))
    )
    (net (code "22") (name "/DJ1_KC33") (class "Default")
      (node (ref "P49") (pin "1") (pinfunction "1_1") (pintype "passive"))
      (node (ref "Q3") (pin "3") (pinfunction "D_3") (pintype "passive"))
      (node (ref "R32") (pin "1") (pintype "passive"))
    )
    (net (code "23") (name "/DJ2_KC1") (class "Default")
      (node (ref "P6") (pin "7") (pinfunction "7_7") (pintype "passive"))
      (node (ref "Q4") (pin "2") (pinfunction "S_2") (pintype "passive"))
      (node (ref "R36") (pin "1") (pintype "passive"))
    )
    (net (code "24") (name "/DJ2_KC2") (class "Default")
      (node (ref "P36") (pin "16") (pinfunction "16_16") (pintype "passive"))
      (node (ref "Q5") (pin "2") (pinfunction "S_2") (pintype "passive"))
      (node (ref "R40") (pin "1") (pintype "passive"))
    )
    (net (code "25") (name "/DJ2_KC3") (class "Default")
      (node (ref "P36") (pin "15") (pinfunction "15_15") (pintype "passive"))
      (node (ref "Q7") (pin "2") (pinfunction "S_2") (pintype "passive"))
      (node (ref "R48") (pin "1") (pintype "passive"))
    )
    (net (code "26") (name "/DJ2_KC11") (class "Default")
      (node (ref "P51") (pin "3") (pinfunction "3_3") (pintype "passive"))
      (node (ref "Q4") (pin "3") (pinfunction "D_3") (pintype "passive"))
      (node (ref "R35") (pin "1") (pintype "passive"))
    )
    (net (code "27") (name "/DJ2_KC22") (class "Default")
      (node (ref "P51") (pin "2") (pinfunction "2_2") (pintype "passive"))
      (node (ref "Q5") (pin "3") (pinfunction "D_3") (pintype "passive"))
      (node (ref "R39") (pin "1") (pintype "passive"))
    )
    (net (code "28") (name "/DJ2_KC33") (class "Default")
      (node (ref "P51") (pin "1") (pinfunction "1_1") (pintype "passive"))
      (node (ref "Q7") (pin "3") (pinfunction "D_3") (pintype "passive"))
      (node (ref "R45") (pin "1") (pintype "passive"))
    )
    (net (code "29") (name "/DJ3_KC1") (class "Default")
      (node (ref "P6") (pin "8") (pinfunction "8_8") (pintype "passive"))
      (node (ref "Q9") (pin "2") (pinfunction "S_2") (pintype "passive"))
      (node (ref "R60") (pin "1") (pintype "passive"))
    )
    (net (code "30") (name "/DJ3_KC2") (class "Default")
      (node (ref "P36") (pin "12") (pinfunction "12_12") (pintype "passive"))
      (node (ref "Q11") (pin "2") (pinfunction "S_2") (pintype "passive"))
      (node (ref "R70") (pin "1") (pintype "passive"))
    )
    (net (code "31") (name "/DJ3_KC3") (class "Default")
      (node (ref "P36") (pin "11") (pinfunction "11_11") (pintype "passive"))
      (node (ref "Q13") (pin "2") (pinfunction "S_2") (pintype "passive"))
      (node (ref "R77") (pin "1") (pintype "passive"))
    )
    (net (code "32") (name "/DJ3_KC11") (class "Default")
      (node (ref "P52") (pin "3") (pinfunction "3_3") (pintype "passive"))
      (node (ref "Q9") (pin "3") (pinfunction "D_3") (pintype "passive"))
      (node (ref "R59") (pin "1") (pintype "passive"))
    )
    (net (code "33") (name "/DJ3_KC22") (class "Default")
      (node (ref "P52") (pin "2") (pinfunction "2_2") (pintype "passive"))
      (node (ref "Q11") (pin "3") (pinfunction "D_3") (pintype "passive"))
      (node (ref "R69") (pin "1") (pintype "passive"))
    )
    (net (code "34") (name "/DJ3_KC33") (class "Default")
      (node (ref "P52") (pin "1") (pinfunction "1_1") (pintype "passive"))
      (node (ref "Q13") (pin "3") (pinfunction "D_3") (pintype "passive"))
      (node (ref "R76") (pin "1") (pintype "passive"))
    )
    (net (code "35") (name "/DJ4_KC1") (class "Default")
      (node (ref "P6") (pin "9") (pinfunction "9_9") (pintype "passive"))
      (node (ref "Q14") (pin "2") (pinfunction "S_2") (pintype "passive"))
      (node (ref "R81") (pin "1") (pintype "passive"))
    )
    (net (code "36") (name "/DJ4_KC2") (class "Default")
      (node (ref "P36") (pin "18") (pinfunction "18_18") (pintype "passive"))
      (node (ref "Q15") (pin "2") (pinfunction "S_2") (pintype "passive"))
      (node (ref "R85") (pin "1") (pintype "passive"))
    )
    (net (code "37") (name "/DJ4_KC3") (class "Default")
      (node (ref "P36") (pin "17") (pinfunction "17_17") (pintype "passive"))
      (node (ref "Q16") (pin "2") (pinfunction "S_2") (pintype "passive"))
      (node (ref "R88") (pin "1") (pintype "passive"))
    )
    (net (code "38") (name "/DJ4_KC11") (class "Default")
      (node (ref "P54") (pin "3") (pinfunction "3_3") (pintype "passive"))
      (node (ref "Q14") (pin "3") (pinfunction "D_3") (pintype "passive"))
      (node (ref "R80") (pin "1") (pintype "passive"))
    )
    (net (code "39") (name "/DJ4_KC22") (class "Default")
      (node (ref "P54") (pin "2") (pinfunction "2_2") (pintype "passive"))
      (node (ref "Q15") (pin "3") (pinfunction "D_3") (pintype "passive"))
      (node (ref "R84") (pin "1") (pintype "passive"))
    )
    (net (code "40") (name "/DJ4_KC33") (class "Default")
      (node (ref "P54") (pin "1") (pinfunction "1_1") (pintype "passive"))
      (node (ref "Q16") (pin "3") (pinfunction "D_3") (pintype "passive"))
      (node (ref "R87") (pin "1") (pintype "passive"))
    )
    (net (code "41") (name "/DWQ1") (class "Default")
      (node (ref "P36") (pin "9") (pinfunction "9_9") (pintype "passive"))
      (node (ref "P44") (pin "2") (pinfunction "2_2") (pintype "passive"))
    )
    (net (code "42") (name "/DWQ2") (class "Default")
      (node (ref "P36") (pin "10") (pinfunction "10_10") (pintype "passive"))
      (node (ref "P46") (pin "2") (pinfunction "2_2") (pintype "passive"))
    )
    (net (code "43") (name "/INPUT_1") (class "Default")
      (node (ref "P1") (pin "3") (pinfunction "3_3") (pintype "passive"))
      (node (ref "P6") (pin "3") (pinfunction "3_3") (pintype "passive"))
    )
    (net (code "44") (name "/INPUT_2") (class "Default")
      (node (ref "P1") (pin "4") (pinfunction "4_4") (pintype "passive"))
      (node (ref "U1") (pin "3") (pinfunction "C2_3") (pintype "passive"))
    )
    (net (code "45") (name "/INPUT_3") (class "Default")
      (node (ref "P1") (pin "5") (pinfunction "5_5") (pintype "passive"))
      (node (ref "U1") (pin "2") (pinfunction "C1_2") (pintype "passive"))
    )
    (net (code "46") (name "/INPUT_4") (class "Default")
      (node (ref "P6") (pin "10") (pinfunction "10_10") (pintype "passive"))
      (node (ref "R57") (pin "1") (pintype "passive"))
      (node (ref "U18") (pin "4") (pintype "passive"))
    )
    (net (code "47") (name "/INPUT_5") (class "Default")
      (node (ref "P6") (pin "11") (pinfunction "11_11") (pintype "passive"))
      (node (ref "R65") (pin "1") (pintype "passive"))
      (node (ref "U23") (pin "4") (pintype "passive"))
    )
    (net (code "48") (name "/INPUT_6") (class "Default")
      (node (ref "P6") (pin "12") (pinfunction "12_12") (pintype "passive"))
      (node (ref "R49") (pin "1") (pintype "passive"))
      (node (ref "U15") (pin "4") (pintype "passive"))
    )
    (net (code "49") (name "/INPUT_7") (class "Default")
      (node (ref "P6") (pin "13") (pinfunction "13_13") (pintype "passive"))
      (node (ref "R66") (pin "1") (pintype "passive"))
      (node (ref "U24") (pin "4") (pintype "passive"))
    )
    (net (code "50") (name "/INPUT_8") (class "Default")
      (node (ref "P6") (pin "14") (pinfunction "14_14") (pintype "passive"))
      (node (ref "R74") (pin "1") (pintype "passive"))
      (node (ref "U28") (pin "4") (pintype "passive"))
    )
    (net (code "51") (name "/INPUT_9") (class "Default")
      (node (ref "P6") (pin "15") (pinfunction "15_15") (pintype "passive"))
      (node (ref "R82") (pin "1") (pintype "passive"))
      (node (ref "U32") (pin "4") (pintype "passive"))
    )
    (net (code "52") (name "/INPUT_10") (class "Default")
      (node (ref "P6") (pin "16") (pinfunction "16_16") (pintype "passive"))
      (node (ref "R50") (pin "1") (pintype "passive"))
      (node (ref "U16") (pin "4") (pintype "passive"))
    )
    (net (code "53") (name "/INPUT_11") (class "Default")
      (node (ref "P6") (pin "17") (pinfunction "17_17") (pintype "passive"))
    )
    (net (code "54") (name "/INPUT_12") (class "Default")
      (node (ref "P1") (pin "6") (pinfunction "6_6") (pintype "passive"))
      (node (ref "P6") (pin "18") (pinfunction "18_18") (pintype "passive"))
    )
    (net (code "55") (name "/INPUT_13") (class "Default")
      (node (ref "P1") (pin "7") (pinfunction "7_7") (pintype "passive"))
      (node (ref "U2") (pin "3") (pinfunction "C2_3") (pintype "passive"))
    )
    (net (code "56") (name "/INPUT_14") (class "Default")
      (node (ref "P1") (pin "8") (pinfunction "8_8") (pintype "passive"))
      (node (ref "U2") (pin "2") (pinfunction "C1_2") (pintype "passive"))
    )
    (net (code "57") (name "/INPUT_17") (class "Default")
      (node (ref "P6") (pin "24") (pinfunction "24_24") (pintype "passive"))
      (node (ref "R58") (pin "1") (pintype "passive"))
      (node (ref "U20") (pin "4") (pintype "passive"))
    )
    (net (code "58") (name "/INPUT_18") (class "Default")
      (node (ref "P6") (pin "25") (pinfunction "25_25") (pintype "passive"))
    )
    (net (code "59") (name "/INPUT_19") (class "Default")
      (node (ref "P2") (pin "4") (pinfunction "4_4") (pintype "passive"))
      (node (ref "U3") (pin "3") (pinfunction "C2_3") (pintype "passive"))
    )
    (net (code "60") (name "/INPUT_20") (class "Default")
      (node (ref "P2") (pin "3") (pinfunction "3_3") (pintype "passive"))
      (node (ref "P6") (pin "31") (pinfunction "31_31") (pintype "passive"))
    )
    (net (code "61") (name "/INPUT_21") (class "Default")
      (node (ref "P2") (pin "5") (pinfunction "5_5") (pintype "passive"))
      (node (ref "U3") (pin "2") (pinfunction "C1_2") (pintype "passive"))
    )
    (net (code "62") (name "/INPUT_22") (class "Default")
      (node (ref "P2") (pin "7") (pinfunction "7_7") (pintype "passive"))
      (node (ref "U4") (pin "3") (pinfunction "C2_3") (pintype "passive"))
    )
    (net (code "63") (name "/INPUT_23") (class "Default")
      (node (ref "P2") (pin "8") (pinfunction "8_8") (pintype "passive"))
      (node (ref "U4") (pin "2") (pinfunction "C1_2") (pintype "passive"))
    )
    (net (code "64") (name "/INPUT_24") (class "Default")
      (node (ref "P2") (pin "6") (pinfunction "6_6") (pintype "passive"))
      (node (ref "P6") (pin "35") (pinfunction "35_35") (pintype "passive"))
    )
    (net (code "65") (name "/IN_2") (class "Default")
      (node (ref "P6") (pin "4") (pinfunction "4_4") (pintype "passive"))
      (node (ref "R13") (pin "1") (pintype "passive"))
      (node (ref "U1") (pin "6") (pinfunction "VO2_6") (pintype "passive"))
    )
    (net (code "66") (name "/IN_3") (class "Default")
      (node (ref "P6") (pin "5") (pinfunction "5_5") (pintype "passive"))
      (node (ref "R15") (pin "2") (pintype "passive"))
      (node (ref "U1") (pin "7") (pinfunction "VO1_7") (pintype "passive"))
    )
    (net (code "67") (name "/IN_13") (class "Default")
      (node (ref "P6") (pin "19") (pinfunction "19_19") (pintype "passive"))
      (node (ref "R14") (pin "1") (pintype "passive"))
      (node (ref "U2") (pin "6") (pinfunction "VO2_6") (pintype "passive"))
    )
    (net (code "68") (name "/IN_14") (class "Default")
      (node (ref "P6") (pin "20") (pinfunction "20_20") (pintype "passive"))
      (node (ref "R16") (pin "2") (pintype "passive"))
      (node (ref "U2") (pin "7") (pinfunction "VO1_7") (pintype "passive"))
    )
    (net (code "69") (name "/IN_19") (class "Default")
      (node (ref "P6") (pin "30") (pinfunction "30_30") (pintype "passive"))
      (node (ref "R21") (pin "1") (pintype "passive"))
      (node (ref "U3") (pin "6") (pinfunction "VO2_6") (pintype "passive"))
    )
    (net (code "70") (name "/IN_21") (class "Default")
      (node (ref "P6") (pin "32") (pinfunction "32_32") (pintype "passive"))
      (node (ref "R23") (pin "2") (pintype "passive"))
      (node (ref "U3") (pin "7") (pinfunction "VO1_7") (pintype "passive"))
    )
    (net (code "71") (name "/IN_22") (class "Default")
      (node (ref "P6") (pin "33") (pinfunction "33_33") (pintype "passive"))
      (node (ref "R22") (pin "1") (pintype "passive"))
      (node (ref "U4") (pin "6") (pinfunction "VO2_6") (pintype "passive"))
    )
    (net (code "72") (name "/IN_23") (class "Default")
      (node (ref "P6") (pin "34") (pinfunction "34_34") (pintype "passive"))
      (node (ref "R24") (pin "2") (pintype "passive"))
      (node (ref "U4") (pin "7") (pinfunction "VO1_7") (pintype "passive"))
    )
    (net (code "73") (name "/JT_KR1") (class "Default")
      (node (ref "D14") (pin "K") (pinfunction "K_K") (pintype "passive"))
      (node (ref "P47") (pin "1") (pinfunction "1_1") (pintype "passive"))
    )
    (net (code "74") (name "/LDAC") (class "Default")
      (node (ref "P6") (pin "29") (pinfunction "29_29") (pintype "passive"))
      (node (ref "U5") (pin "13") (pinfunction "LDAC_13") (pintype "passive"))
    )
    (net (code "75") (name "/LOAD") (class "Default")
      (node (ref "P6") (pin "28") (pinfunction "28_28") (pintype "passive"))
      (node (ref "U5") (pin "8") (pinfunction "LOAD_8") (pintype "passive"))
    )
    (net (code "76") (name "/O13") (class "Default")
      (node (ref "R98") (pin "1") (pinfunction "1_1") (pintype "passive"))
      (node (ref "U41") (pin "2") (pinfunction "G1_2") (pintype "passive"))
    )
    (net (code "77") (name "/O14") (class "Default")
      (node (ref "R102") (pin "1") (pinfunction "1_1") (pintype "passive"))
      (node (ref "U44") (pin "4") (pinfunction "G2_4") (pintype "passive"))
    )
    (net (code "78") (name "/O15") (class "Default")
      (node (ref "R107") (pin "1") (pinfunction "1_1") (pintype "passive"))
      (node (ref "U44") (pin "2") (pinfunction "G1_2") (pintype "passive"))
    )
    (net (code "79") (name "/O16") (class "Default")
      (node (ref "R111") (pin "1") (pinfunction "1_1") (pintype "passive"))
      (node (ref "U41") (pin "4") (pinfunction "G2_4") (pintype "passive"))
    )
    (net (code "80") (name "/O17") (class "Default")
      (node (ref "R116") (pin "1") (pinfunction "1_1") (pintype "passive"))
      (node (ref "U47") (pin "4") (pinfunction "G2_4") (pintype "passive"))
    )
    (net (code "81") (name "/O18") (class "Default")
      (node (ref "R123") (pin "1") (pinfunction "1_1") (pintype "passive"))
      (node (ref "U47") (pin "2") (pinfunction "G1_2") (pintype "passive"))
    )
    (net (code "82") (name "/O19") (class "Default")
      (node (ref "R127") (pin "1") (pinfunction "1_1") (pintype "passive"))
      (node (ref "U51") (pin "4") (pinfunction "G2_4") (pintype "passive"))
    )
    (net (code "83") (name "/O20") (class "Default")
      (node (ref "R133") (pin "1") (pinfunction "1_1") (pintype "passive"))
      (node (ref "U51") (pin "2") (pinfunction "G1_2") (pintype "passive"))
    )
    (net (code "84") (name "/O21") (class "Default")
      (node (ref "R139") (pin "1") (pinfunction "1_1") (pintype "passive"))
      (node (ref "U55") (pin "4") (pinfunction "G2_4") (pintype "passive"))
    )
    (net (code "85") (name "/O22") (class "Default")
      (node (ref "R143") (pin "1") (pinfunction "1_1") (pintype "passive"))
      (node (ref "U55") (pin "2") (pinfunction "G1_2") (pintype "passive"))
    )
    (net (code "86") (name "/PWM1") (class "Default")
      (node (ref "P36") (pin "30") (pinfunction "30_30") (pintype "passive"))
      (node (ref "Q6") (pin "2") (pinfunction "S_2") (pintype "passive"))
      (node (ref "R42") (pin "1") (pintype "passive"))
    )
    (net (code "87") (name "/PWM2") (class "Default")
      (node (ref "P36") (pin "29") (pinfunction "29_29") (pintype "passive"))
      (node (ref "Q8") (pin "2") (pinfunction "S_2") (pintype "passive"))
      (node (ref "R53") (pin "1") (pintype "passive"))
    )
    (net (code "88") (name "/PWM3") (class "Default")
      (node (ref "P36") (pin "28") (pinfunction "28_28") (pintype "passive"))
      (node (ref "Q10") (pin "2") (pinfunction "S_2") (pintype "passive"))
      (node (ref "R64") (pin "1") (pintype "passive"))
    )
    (net (code "89") (name "/PWM4") (class "Default")
      (node (ref "P36") (pin "27") (pinfunction "27_27") (pintype "passive"))
      (node (ref "Q12") (pin "2") (pinfunction "S_2") (pintype "passive"))
      (node (ref "R73") (pin "1") (pintype "passive"))
    )
    (net (code "90") (name "/PWM11") (class "Default")
      (node (ref "P49") (pin "4") (pinfunction "4_4") (pintype "passive"))
      (node (ref "Q6") (pin "3") (pinfunction "D_3") (pintype "passive"))
      (node (ref "R41") (pin "1") (pintype "passive"))
    )
    (net (code "91") (name "/PWM22") (class "Default")
      (node (ref "P51") (pin "4") (pinfunction "4_4") (pintype "passive"))
      (node (ref "Q8") (pin "3") (pinfunction "D_3") (pintype "passive"))
      (node (ref "R51") (pin "1") (pintype "passive"))
    )
    (net (code "92") (name "/PWM33") (class "Default")
      (node (ref "P52") (pin "4") (pinfunction "4_4") (pintype "passive"))
      (node (ref "Q10") (pin "3") (pinfunction "D_3") (pintype "passive"))
      (node (ref "R61") (pin "1") (pintype "passive"))
    )
    (net (code "93") (name "/PWM44") (class "Default")
      (node (ref "P54") (pin "4") (pinfunction "4_4") (pintype "passive"))
      (node (ref "Q12") (pin "3") (pinfunction "D_3") (pintype "passive"))
      (node (ref "R72") (pin "1") (pintype "passive"))
    )
    (net (code "94") (name "/QD_KR1") (class "Default")
      (node (ref "D22") (pin "K") (pinfunction "K_K") (pintype "passive"))
      (node (ref "P43") (pin "1") (pinfunction "1_1") (pintype "passive"))
    )
    (net (code "95") (name "/QYG_KC1") (class "Default")
      (node (ref "P6") (pin "36") (pinfunction "36_36") (pintype "passive"))
      (node (ref "U40") (pin "2") (pintype "passive"))
    )
    (net (code "96") (name "/QYG_KC11") (class "Default")
      (node (ref "D56") (pin "1") (pinfunction "A_1") (pintype "passive"))
      (node (ref "P53") (pin "3") (pinfunction "3_3") (pintype "passive"))
      (node (ref "R5") (pin "2") (pintype "passive"))
      (node (ref "U41") (pin "7") (pinfunction "D1_7") (pintype "passive"))
      (node (ref "U41") (pin "8") (pinfunction "D1_8") (pintype "passive"))
    )
    (net (code "97") (name "/QYG_KR1") (class "Default")
      (node (ref "D15") (pin "K") (pinfunction "K_K") (pintype "passive"))
      (node (ref "P53") (pin "4") (pinfunction "4_4") (pintype "passive"))
    )
    (net (code "98") (name "/QYG_KR2") (class "Default")
      (node (ref "D19") (pin "K") (pinfunction "K_K") (pintype "passive"))
      (node (ref "P53") (pin "5") (pinfunction "5_5") (pintype "passive"))
    )
    (net (code "99") (name "/RS485_1A") (class "Default")
      (node (ref "P36") (pin "7") (pinfunction "7_7") (pintype "passive"))
      (node (ref "P60") (pin "4") (pinfunction "4_4") (pintype "passive"))
    )
    (net (code "100") (name "/RS485_1B") (class "Default")
      (node (ref "P36") (pin "8") (pinfunction "8_8") (pintype "passive"))
      (node (ref "P60") (pin "3") (pinfunction "3_3") (pintype "passive"))
    )
    (net (code "101") (name "/SSD_KC1") (class "Default")
      (node (ref "P36") (pin "24") (pinfunction "24_24") (pintype "passive"))
      (node (ref "U46") (pin "2") (pintype "passive"))
    )
    (net (code "102") (name "/SSD_KC2") (class "Default")
      (node (ref "P36") (pin "23") (pinfunction "23_23") (pintype "passive"))
      (node (ref "U49") (pin "2") (pintype "passive"))
    )
    (net (code "103") (name "/SSD_KC3") (class "Default")
      (node (ref "P36") (pin "22") (pinfunction "22_22") (pintype "passive"))
      (node (ref "U50") (pin "2") (pintype "passive"))
    )
    (net (code "104") (name "/SSD_KC11") (class "Default")
      (node (ref "D46") (pin "1") (pinfunction "A_1") (pintype "passive"))
      (node (ref "P48") (pin "2") (pinfunction "2_2") (pintype "passive"))
      (node (ref "U47") (pin "5") (pinfunction "D2_5") (pintype "passive"))
      (node (ref "U47") (pin "6") (pinfunction "D2_6") (pintype "passive"))
    )
    (net (code "105") (name "/SSD_KC22") (class "Default")
      (node (ref "D48") (pin "1") (pinfunction "A_1") (pintype "passive"))
      (node (ref "P48") (pin "3") (pinfunction "3_3") (pintype "passive"))
      (node (ref "U47") (pin "7") (pinfunction "D1_7") (pintype "passive"))
      (node (ref "U47") (pin "8") (pinfunction "D1_8") (pintype "passive"))
    )
    (net (code "106") (name "/SSD_KC33") (class "Default")
      (node (ref "D50") (pin "1") (pinfunction "A_1") (pintype "passive"))
      (node (ref "P48") (pin "4") (pinfunction "4_4") (pintype "passive"))
      (node (ref "U51") (pin "5") (pinfunction "D2_5") (pintype "passive"))
      (node (ref "U51") (pin "6") (pinfunction "D2_6") (pintype "passive"))
    )
    (net (code "107") (name "/SpeekR+") (class "Default")
      (node (ref "P36") (pin "6") (pinfunction "6_6") (pintype "passive"))
      (node (ref "P42") (pin "1") (pinfunction "1_1") (pintype "passive"))
    )
    (net (code "108") (name "/SpeekR-") (class "Default")
      (node (ref "P36") (pin "5") (pinfunction "5_5") (pintype "passive"))
      (node (ref "P42") (pin "2") (pinfunction "2_2") (pintype "passive"))
    )
    (net (code "109") (name "/TXX_KC1") (class "Default")
      (node (ref "P6") (pin "21") (pinfunction "21_21") (pintype "passive"))
      (node (ref "U42") (pin "2") (pintype "passive"))
    )
    (net (code "110") (name "/TXX_KC2") (class "Default")
      (node (ref "P6") (pin "22") (pinfunction "22_22") (pintype "passive"))
      (node (ref "U43") (pin "2") (pintype "passive"))
    )
    (net (code "111") (name "/TXX_KC3") (class "Default")
      (node (ref "P6") (pin "23") (pinfunction "23_23") (pintype "passive"))
      (node (ref "U45") (pin "2") (pintype "passive"))
    )
    (net (code "112") (name "/TXX_KC11") (class "Default")
      (node (ref "D52") (pin "1") (pinfunction "A_1") (pintype "passive"))
      (node (ref "P50") (pin "4") (pinfunction "4_4") (pintype "passive"))
      (node (ref "R8") (pin "1") (pintype "passive"))
      (node (ref "U44") (pin "5") (pinfunction "D2_5") (pintype "passive"))
      (node (ref "U44") (pin "6") (pinfunction "D2_6") (pintype "passive"))
    )
    (net (code "113") (name "/TXX_KC22") (class "Default")
      (node (ref "D53") (pin "1") (pinfunction "A_1") (pintype "passive"))
      (node (ref "P50") (pin "5") (pinfunction "5_5") (pintype "passive"))
      (node (ref "R7") (pin "2") (pintype "passive"))
      (node (ref "U44") (pin "7") (pinfunction "D1_7") (pintype "passive"))
      (node (ref "U44") (pin "8") (pinfunction "D1_8") (pintype "passive"))
    )
    (net (code "114") (name "/TXX_KC33") (class "Default")
      (node (ref "D55") (pin "1") (pinfunction "A_1") (pintype "passive"))
      (node (ref "P50") (pin "6") (pinfunction "6_6") (pintype "passive"))
      (node (ref "R6") (pin "1") (pintype "passive"))
      (node (ref "U41") (pin "5") (pinfunction "D2_5") (pintype "passive"))
      (node (ref "U41") (pin "6") (pinfunction "D2_6") (pintype "passive"))
    )
    (net (code "115") (name "/TXX_KR1") (class "Default")
      (node (ref "D23") (pin "K") (pinfunction "K_K") (pintype "passive"))
      (node (ref "P50") (pin "1") (pinfunction "1_1") (pintype "passive"))
    )
    (net (code "116") (name "/TXX_KR2") (class "Default")
      (node (ref "D27") (pin "K") (pinfunction "K_K") (pintype "passive"))
      (node (ref "P50") (pin "2") (pinfunction "2_2") (pintype "passive"))
    )
    (net (code "117") (name "/TXX_KR3") (class "Default")
      (node (ref "D32") (pin "K") (pinfunction "K_K") (pintype "passive"))
      (node (ref "P50") (pin "3") (pinfunction "3_3") (pintype "passive"))
    )
    (net (code "118") (name "/TZ_KR1") (class "Default")
      (node (ref "D18") (pin "K") (pinfunction "K_K") (pintype "passive"))
      (node (ref "P45") (pin "1") (pinfunction "1_1") (pintype "passive"))
    )
    (net (code "119") (name "/U2_RX") (class "Default")
      (node (ref "P36") (pin "3") (pinfunction "3_3") (pintype "passive"))
      (node (ref "P62") (pin "4") (pinfunction "4_4") (pintype "passive"))
    )
    (net (code "120") (name "/U2_TX") (class "Default")
      (node (ref "P36") (pin "4") (pinfunction "4_4") (pintype "passive"))
      (node (ref "P62") (pin "3") (pinfunction "3_3") (pintype "passive"))
    )
    (net (code "121") (name "GND24_B") (class "Default")
      (node (ref "C1") (pin "1") (pintype "passive"))
      (node (ref "C2") (pin "2") (pinfunction "GND_2") (pintype "passive"))
      (node (ref "C3") (pin "2") (pintype "passive"))
      (node (ref "C4") (pin "1") (pintype "passive"))
      (node (ref "C5") (pin "1") (pintype "passive"))
      (node (ref "C6") (pin "1") (pintype "passive"))
      (node (ref "D41") (pin "K") (pinfunction "K_K") (pintype "passive"))
      (node (ref "J4") (pin "2") (pinfunction "2_2") (pintype "passive"))
      (node (ref "P1") (pin "2") (pinfunction "2_2") (pintype "passive"))
      (node (ref "P2") (pin "2") (pinfunction "2_2") (pintype "passive"))
      (node (ref "P3") (pin "5") (pinfunction "5_5") (pintype "passive"))
      (node (ref "P36") (pin "2") (pinfunction "2_2") (pintype "passive"))
      (node (ref "P38") (pin "2") (pinfunction "2_2") (pintype "passive"))
      (node (ref "P4") (pin "2") (pinfunction "2_2") (pintype "passive"))
      (node (ref "P43") (pin "2") (pinfunction "2_2") (pintype "passive"))
      (node (ref "P44") (pin "1") (pinfunction "1_1") (pintype "passive"))
      (node (ref "P45") (pin "2") (pinfunction "2_2") (pintype "passive"))
      (node (ref "P46") (pin "1") (pinfunction "1_1") (pintype "passive"))
      (node (ref "P47") (pin "2") (pinfunction "2_2") (pintype "passive"))
      (node (ref "P49") (pin "5") (pinfunction "5_5") (pintype "passive"))
      (node (ref "P50") (pin "7") (pinfunction "7_7") (pintype "passive"))
      (node (ref "P51") (pin "5") (pinfunction "5_5") (pintype "passive"))
      (node (ref "P52") (pin "5") (pinfunction "5_5") (pintype "passive"))
      (node (ref "P53") (pin "2") (pinfunction "2_2") (pintype "passive"))
      (node (ref "P54") (pin "5") (pinfunction "5_5") (pintype "passive"))
      (node (ref "P60") (pin "2") (pinfunction "2_2") (pintype "passive"))
      (node (ref "P61") (pin "2") (pinfunction "2_2") (pintype "passive"))
      (node (ref "P62") (pin "2") (pinfunction "2_2") (pintype "passive"))
      (node (ref "R103") (pin "1") (pintype "passive"))
      (node (ref "R108") (pin "1") (pintype "passive"))
      (node (ref "R112") (pin "1") (pintype "passive"))
      (node (ref "R118") (pin "1") (pintype "passive"))
      (node (ref "R124") (pin "1") (pintype "passive"))
      (node (ref "R128") (pin "1") (pintype "passive"))
      (node (ref "R135") (pin "1") (pintype "passive"))
      (node (ref "R140") (pin "1") (pintype "passive"))
      (node (ref "R144") (pin "1") (pintype "passive"))
      (node (ref "R99") (pin "1") (pintype "passive"))
      (node (ref "U1") (pin "5") (pinfunction "GND_5") (pintype "passive"))
      (node (ref "U15") (pin "3") (pintype "passive"))
      (node (ref "U16") (pin "3") (pintype "passive"))
      (node (ref "U18") (pin "3") (pintype "passive"))
      (node (ref "U2") (pin "5") (pinfunction "GND_5") (pintype "passive"))
      (node (ref "U20") (pin "3") (pintype "passive"))
      (node (ref "U23") (pin "3") (pintype "passive"))
      (node (ref "U24") (pin "3") (pintype "passive"))
      (node (ref "U28") (pin "3") (pintype "passive"))
      (node (ref "U3") (pin "5") (pinfunction "GND_5") (pintype "passive"))
      (node (ref "U32") (pin "3") (pintype "passive"))
      (node (ref "U4") (pin "5") (pinfunction "GND_5") (pintype "passive"))
      (node (ref "U41") (pin "1") (pinfunction "S1_1") (pintype "passive"))
      (node (ref "U41") (pin "3") (pinfunction "S2_3") (pintype "passive"))
      (node (ref "U44") (pin "1") (pinfunction "S1_1") (pintype "passive"))
      (node (ref "U44") (pin "3") (pinfunction "S2_3") (pintype "passive"))
      (node (ref "U47") (pin "1") (pinfunction "S1_1") (pintype "passive"))
      (node (ref "U47") (pin "3") (pinfunction "S2_3") (pintype "passive"))
      (node (ref "U5") (pin "1") (pinfunction "GND_1") (pintype "passive"))
      (node (ref "U51") (pin "1") (pinfunction "S1_1") (pintype "passive"))
      (node (ref "U51") (pin "3") (pinfunction "S2_3") (pintype "passive"))
      (node (ref "U55") (pin "1") (pinfunction "S1_1") (pintype "passive"))
      (node (ref "U55") (pin "3") (pinfunction "S2_3") (pintype "passive"))
    )
    (net (code "122") (name "Net-(D1-K)") (class "Default")
      (node (ref "D1") (pin "2") (pinfunction "K_2") (pintype "passive"))
      (node (ref "F1") (pin "1") (pinfunction "1_1") (pintype "passive"))
    )
    (net (code "123") (name "Net-(D14-PadA)") (class "Default")
      (node (ref "D14") (pin "A") (pinfunction "A_A") (pintype "passive"))
      (node (ref "U15") (pin "2") (pintype "passive"))
    )
    (net (code "124") (name "Net-(D15-PadA)") (class "Default")
      (node (ref "D15") (pin "A") (pinfunction "A_A") (pintype "passive"))
      (node (ref "U16") (pin "2") (pintype "passive"))
    )
    (net (code "125") (name "Net-(D18-PadA)") (class "Default")
      (node (ref "D18") (pin "A") (pinfunction "A_A") (pintype "passive"))
      (node (ref "U18") (pin "2") (pintype "passive"))
    )
    (net (code "126") (name "Net-(D19-PadA)") (class "Default")
      (node (ref "D19") (pin "A") (pinfunction "A_A") (pintype "passive"))
      (node (ref "U20") (pin "2") (pintype "passive"))
    )
    (net (code "127") (name "Net-(D22-PadA)") (class "Default")
      (node (ref "D22") (pin "A") (pinfunction "A_A") (pintype "passive"))
      (node (ref "U23") (pin "2") (pintype "passive"))
    )
    (net (code "128") (name "Net-(D23-PadA)") (class "Default")
      (node (ref "D23") (pin "A") (pinfunction "A_A") (pintype "passive"))
      (node (ref "U24") (pin "2") (pintype "passive"))
    )
    (net (code "129") (name "Net-(D27-PadA)") (class "Default")
      (node (ref "D27") (pin "A") (pinfunction "A_A") (pintype "passive"))
      (node (ref "U28") (pin "2") (pintype "passive"))
    )
    (net (code "130") (name "Net-(D32-PadA)") (class "Default")
      (node (ref "D32") (pin "A") (pinfunction "A_A") (pintype "passive"))
      (node (ref "U32") (pin "2") (pintype "passive"))
    )
    (net (code "131") (name "Net-(D39-PadK)") (class "Default")
      (node (ref "D39") (pin "K") (pinfunction "K_K") (pintype "passive"))
      (node (ref "R97") (pin "1") (pintype "passive"))
    )
    (net (code "132") (name "Net-(D40-PadK)") (class "Default")
      (node (ref "D40") (pin "K") (pinfunction "K_K") (pintype "passive"))
      (node (ref "R101") (pin "2") (pintype "passive"))
    )
    (net (code "133") (name "Net-(D41-PadA)") (class "Default")
      (node (ref "D41") (pin "A") (pinfunction "A_A") (pintype "passive"))
      (node (ref "R106") (pin "2") (pinfunction "2_2") (pintype "passive"))
    )
    (net (code "134") (name "Net-(D42-PadK)") (class "Default")
      (node (ref "D42") (pin "K") (pinfunction "K_K") (pintype "passive"))
      (node (ref "R105") (pin "1") (pintype "passive"))
    )
    (net (code "135") (name "Net-(D43-PadK)") (class "Default")
      (node (ref "D43") (pin "K") (pinfunction "K_K") (pintype "passive"))
      (node (ref "R110") (pin "2") (pintype "passive"))
    )
    (net (code "136") (name "Net-(D49-PadK)") (class "Default")
      (node (ref "D49") (pin "K") (pinfunction "K_K") (pintype "passive"))
      (node (ref "R114") (pin "1") (pintype "passive"))
    )
    (net (code "137") (name "Net-(D51-PadK)") (class "Default")
      (node (ref "D51") (pin "K") (pinfunction "K_K") (pintype "passive"))
      (node (ref "R120") (pin "1") (pintype "passive"))
    )
    (net (code "138") (name "Net-(D54-PadK)") (class "Default")
      (node (ref "D54") (pin "K") (pinfunction "K_K") (pintype "passive"))
      (node (ref "R126") (pin "1") (pintype "passive"))
    )
    (net (code "139") (name "Net-(D57-PadK)") (class "Default")
      (node (ref "D57") (pin "K") (pinfunction "K_K") (pintype "passive"))
      (node (ref "R131") (pin "1") (pintype "passive"))
    )
    (net (code "140") (name "Net-(D58-PadK)") (class "Default")
      (node (ref "D58") (pin "K") (pinfunction "K_K") (pintype "passive"))
      (node (ref "R138") (pin "1") (pintype "passive"))
    )
    (net (code "141") (name "Net-(D59-PadK)") (class "Default")
      (node (ref "D59") (pin "K") (pinfunction "K_K") (pintype "passive"))
      (node (ref "R142") (pin "1") (pintype "passive"))
    )
    (net (code "142") (name "Net-(Q1-G)") (class "Default")
      (node (ref "Q1") (pin "1") (pinfunction "G_1") (pintype "passive"))
      (node (ref "R9") (pin "1") (pintype "passive"))
    )
    (net (code "143") (name "Net-(Q2-G)") (class "Default")
      (node (ref "Q2") (pin "1") (pinfunction "G_1") (pintype "passive"))
      (node (ref "R28") (pin "1") (pintype "passive"))
    )
    (net (code "144") (name "Net-(Q3-G)") (class "Default")
      (node (ref "Q3") (pin "1") (pinfunction "G_1") (pintype "passive"))
      (node (ref "R31") (pin "1") (pintype "passive"))
    )
    (net (code "145") (name "Net-(Q4-G)") (class "Default")
      (node (ref "Q4") (pin "1") (pinfunction "G_1") (pintype "passive"))
      (node (ref "R34") (pin "1") (pintype "passive"))
    )
    (net (code "146") (name "Net-(Q5-G)") (class "Default")
      (node (ref "Q5") (pin "1") (pinfunction "G_1") (pintype "passive"))
      (node (ref "R37") (pin "1") (pintype "passive"))
    )
    (net (code "147") (name "Net-(Q6-G)") (class "Default")
      (node (ref "Q6") (pin "1") (pinfunction "G_1") (pintype "passive"))
      (node (ref "R38") (pin "1") (pintype "passive"))
    )
    (net (code "148") (name "Net-(Q7-G)") (class "Default")
      (node (ref "Q7") (pin "1") (pinfunction "G_1") (pintype "passive"))
      (node (ref "R43") (pin "1") (pintype "passive"))
    )
    (net (code "149") (name "Net-(Q8-G)") (class "Default")
      (node (ref "Q8") (pin "1") (pinfunction "G_1") (pintype "passive"))
      (node (ref "R44") (pin "1") (pintype "passive"))
    )
    (net (code "150") (name "Net-(Q9-G)") (class "Default")
      (node (ref "Q9") (pin "1") (pinfunction "G_1") (pintype "passive"))
      (node (ref "R54") (pin "1") (pintype "passive"))
    )
    (net (code "151") (name "Net-(Q10-G)") (class "Default")
      (node (ref "Q10") (pin "1") (pinfunction "G_1") (pintype "passive"))
      (node (ref "R56") (pin "1") (pintype "passive"))
    )
    (net (code "152") (name "Net-(Q11-G)") (class "Default")
      (node (ref "Q11") (pin "1") (pinfunction "G_1") (pintype "passive"))
      (node (ref "R67") (pin "1") (pintype "passive"))
    )
    (net (code "153") (name "Net-(Q12-G)") (class "Default")
      (node (ref "Q12") (pin "1") (pinfunction "G_1") (pintype "passive"))
      (node (ref "R68") (pin "1") (pintype "passive"))
    )
    (net (code "154") (name "Net-(Q13-G)") (class "Default")
      (node (ref "Q13") (pin "1") (pinfunction "G_1") (pintype "passive"))
      (node (ref "R75") (pin "1") (pintype "passive"))
    )
    (net (code "155") (name "Net-(Q14-G)") (class "Default")
      (node (ref "Q14") (pin "1") (pinfunction "G_1") (pintype "passive"))
      (node (ref "R78") (pin "1") (pintype "passive"))
    )
    (net (code "156") (name "Net-(Q15-G)") (class "Default")
      (node (ref "Q15") (pin "1") (pinfunction "G_1") (pintype "passive"))
      (node (ref "R83") (pin "1") (pintype "passive"))
    )
    (net (code "157") (name "Net-(Q16-G)") (class "Default")
      (node (ref "Q16") (pin "1") (pinfunction "G_1") (pintype "passive"))
      (node (ref "R86") (pin "1") (pintype "passive"))
    )
    (net (code "158") (name "Net-(R46-Pad1)") (class "Default")
      (node (ref "R46") (pin "1") (pintype "passive"))
      (node (ref "U15") (pin "1") (pintype "passive"))
    )
    (net (code "159") (name "Net-(R47-Pad1)") (class "Default")
      (node (ref "R47") (pin "1") (pintype "passive"))
      (node (ref "U16") (pin "1") (pintype "passive"))
    )
    (net (code "160") (name "Net-(R52-Pad1)") (class "Default")
      (node (ref "R52") (pin "1") (pintype "passive"))
      (node (ref "U18") (pin "1") (pintype "passive"))
    )
    (net (code "161") (name "Net-(R55-Pad1)") (class "Default")
      (node (ref "R55") (pin "1") (pintype "passive"))
      (node (ref "U20") (pin "1") (pintype "passive"))
    )
    (net (code "162") (name "Net-(R62-Pad1)") (class "Default")
      (node (ref "R62") (pin "1") (pintype "passive"))
      (node (ref "U23") (pin "1") (pintype "passive"))
    )
    (net (code "163") (name "Net-(R63-Pad1)") (class "Default")
      (node (ref "R63") (pin "1") (pintype "passive"))
      (node (ref "U24") (pin "1") (pintype "passive"))
    )
    (net (code "164") (name "Net-(R71-Pad1)") (class "Default")
      (node (ref "R71") (pin "1") (pintype "passive"))
      (node (ref "U28") (pin "1") (pintype "passive"))
    )
    (net (code "165") (name "Net-(R79-Pad1)") (class "Default")
      (node (ref "R79") (pin "1") (pintype "passive"))
      (node (ref "U32") (pin "1") (pintype "passive"))
    )
    (net (code "166") (name "Net-(R96-Pad1)") (class "Default")
      (node (ref "R96") (pin "1") (pintype "passive"))
      (node (ref "U40") (pin "1") (pintype "passive"))
    )
    (net (code "167") (name "Net-(R97-Pad2)") (class "Default")
      (node (ref "R97") (pin "2") (pintype "passive"))
      (node (ref "U42") (pin "4") (pintype "passive"))
    )
    (net (code "168") (name "Net-(R98-Pad2)") (class "Default")
      (node (ref "R98") (pin "2") (pinfunction "2_2") (pintype "passive"))
      (node (ref "R99") (pin "2") (pintype "passive"))
      (node (ref "U40") (pin "3") (pintype "passive"))
    )
    (net (code "169") (name "Net-(R100-Pad1)") (class "Default")
      (node (ref "R100") (pin "1") (pintype "passive"))
      (node (ref "U42") (pin "1") (pintype "passive"))
    )
    (net (code "170") (name "Net-(R101-Pad1)") (class "Default")
      (node (ref "R101") (pin "1") (pintype "passive"))
      (node (ref "U40") (pin "4") (pintype "passive"))
    )
    (net (code "171") (name "Net-(R102-Pad2)") (class "Default")
      (node (ref "R102") (pin "2") (pinfunction "2_2") (pintype "passive"))
      (node (ref "R103") (pin "2") (pintype "passive"))
      (node (ref "U42") (pin "3") (pintype "passive"))
    )
    (net (code "172") (name "Net-(R104-Pad1)") (class "Default")
      (node (ref "R104") (pin "1") (pintype "passive"))
      (node (ref "U43") (pin "1") (pintype "passive"))
    )
    (net (code "173") (name "Net-(R105-Pad2)") (class "Default")
      (node (ref "R105") (pin "2") (pintype "passive"))
      (node (ref "U43") (pin "4") (pintype "passive"))
    )
    (net (code "174") (name "Net-(R107-Pad2)") (class "Default")
      (node (ref "R107") (pin "2") (pinfunction "2_2") (pintype "passive"))
      (node (ref "R108") (pin "2") (pintype "passive"))
      (node (ref "U43") (pin "3") (pintype "passive"))
    )
    (net (code "175") (name "Net-(R109-Pad1)") (class "Default")
      (node (ref "R109") (pin "1") (pintype "passive"))
      (node (ref "U45") (pin "1") (pintype "passive"))
    )
    (net (code "176") (name "Net-(R110-Pad1)") (class "Default")
      (node (ref "R110") (pin "1") (pintype "passive"))
      (node (ref "U45") (pin "4") (pintype "passive"))
    )
    (net (code "177") (name "Net-(R111-Pad2)") (class "Default")
      (node (ref "R111") (pin "2") (pinfunction "2_2") (pintype "passive"))
      (node (ref "R112") (pin "2") (pintype "passive"))
      (node (ref "U45") (pin "3") (pintype "passive"))
    )
    (net (code "178") (name "Net-(R113-Pad1)") (class "Default")
      (node (ref "R113") (pin "1") (pintype "passive"))
      (node (ref "U46") (pin "1") (pintype "passive"))
    )
    (net (code "179") (name "Net-(R114-Pad2)") (class "Default")
      (node (ref "R114") (pin "2") (pintype "passive"))
      (node (ref "U46") (pin "4") (pintype "passive"))
    )
    (net (code "180") (name "Net-(R116-Pad2)") (class "Default")
      (node (ref "R116") (pin "2") (pinfunction "2_2") (pintype "passive"))
      (node (ref "R118") (pin "2") (pintype "passive"))
      (node (ref "U46") (pin "3") (pintype "passive"))
    )
    (net (code "181") (name "Net-(R119-Pad1)") (class "Default")
      (node (ref "R119") (pin "1") (pintype "passive"))
      (node (ref "U49") (pin "1") (pintype "passive"))
    )
    (net (code "182") (name "Net-(R120-Pad2)") (class "Default")
      (node (ref "R120") (pin "2") (pintype "passive"))
      (node (ref "U49") (pin "4") (pintype "passive"))
    )
    (net (code "183") (name "Net-(R123-Pad2)") (class "Default")
      (node (ref "R123") (pin "2") (pinfunction "2_2") (pintype "passive"))
      (node (ref "R124") (pin "2") (pintype "passive"))
      (node (ref "U49") (pin "3") (pintype "passive"))
    )
    (net (code "184") (name "Net-(R125-Pad1)") (class "Default")
      (node (ref "R125") (pin "1") (pintype "passive"))
      (node (ref "U50") (pin "1") (pintype "passive"))
    )
    (net (code "185") (name "Net-(R126-Pad2)") (class "Default")
      (node (ref "R126") (pin "2") (pintype "passive"))
      (node (ref "U53") (pin "4") (pintype "passive"))
    )
    (net (code "186") (name "Net-(R127-Pad2)") (class "Default")
      (node (ref "R127") (pin "2") (pinfunction "2_2") (pintype "passive"))
      (node (ref "R128") (pin "2") (pintype "passive"))
      (node (ref "U50") (pin "3") (pintype "passive"))
    )
    (net (code "187") (name "Net-(R130-Pad1)") (class "Default")
      (node (ref "R130") (pin "1") (pintype "passive"))
      (node (ref "U53") (pin "1") (pintype "passive"))
    )
    (net (code "188") (name "Net-(R131-Pad2)") (class "Default")
      (node (ref "R131") (pin "2") (pintype "passive"))
      (node (ref "U50") (pin "4") (pintype "passive"))
    )
    (net (code "189") (name "Net-(R133-Pad2)") (class "Default")
      (node (ref "R133") (pin "2") (pinfunction "2_2") (pintype "passive"))
      (node (ref "R135") (pin "2") (pintype "passive"))
      (node (ref "U53") (pin "3") (pintype "passive"))
    )
    (net (code "190") (name "Net-(R137-Pad1)") (class "Default")
      (node (ref "R137") (pin "1") (pintype "passive"))
      (node (ref "U54") (pin "1") (pintype "passive"))
    )
    (net (code "191") (name "Net-(R138-Pad2)") (class "Default")
      (node (ref "R138") (pin "2") (pintype "passive"))
      (node (ref "U54") (pin "4") (pintype "passive"))
    )
    (net (code "192") (name "Net-(R139-Pad2)") (class "Default")
      (node (ref "R139") (pin "2") (pinfunction "2_2") (pintype "passive"))
      (node (ref "R140") (pin "2") (pintype "passive"))
      (node (ref "U54") (pin "3") (pintype "passive"))
    )
    (net (code "193") (name "Net-(R141-Pad1)") (class "Default")
      (node (ref "R141") (pin "1") (pintype "passive"))
      (node (ref "U56") (pin "1") (pintype "passive"))
    )
    (net (code "194") (name "Net-(R142-Pad2)") (class "Default")
      (node (ref "R142") (pin "2") (pintype "passive"))
      (node (ref "U56") (pin "4") (pintype "passive"))
    )
    (net (code "195") (name "Net-(R143-Pad2)") (class "Default")
      (node (ref "R143") (pin "2") (pinfunction "2_2") (pintype "passive"))
      (node (ref "R144") (pin "2") (pintype "passive"))
      (node (ref "U56") (pin "3") (pintype "passive"))
    )
    (net (code "196") (name "Net-(U1-A1)") (class "Default")
      (node (ref "R17") (pin "1") (pintype "passive"))
      (node (ref "U1") (pin "1") (pinfunction "A1_1") (pintype "passive"))
    )
    (net (code "197") (name "Net-(U1-A2)") (class "Default")
      (node (ref "R11") (pin "1") (pintype "passive"))
      (node (ref "U1") (pin "4") (pinfunction "A2_4") (pintype "passive"))
    )
    (net (code "198") (name "Net-(U2-A1)") (class "Default")
      (node (ref "R18") (pin "1") (pintype "passive"))
      (node (ref "U2") (pin "1") (pinfunction "A1_1") (pintype "passive"))
    )
    (net (code "199") (name "Net-(U2-A2)") (class "Default")
      (node (ref "R12") (pin "1") (pintype "passive"))
      (node (ref "U2") (pin "4") (pinfunction "A2_4") (pintype "passive"))
    )
    (net (code "200") (name "Net-(U3-A1)") (class "Default")
      (node (ref "R25") (pin "1") (pintype "passive"))
      (node (ref "U3") (pin "1") (pinfunction "A1_1") (pintype "passive"))
    )
    (net (code "201") (name "Net-(U3-A2)") (class "Default")
      (node (ref "R19") (pin "1") (pintype "passive"))
      (node (ref "U3") (pin "4") (pinfunction "A2_4") (pintype "passive"))
    )
    (net (code "202") (name "Net-(U4-A1)") (class "Default")
      (node (ref "R26") (pin "1") (pintype "passive"))
      (node (ref "U4") (pin "1") (pinfunction "A1_1") (pintype "passive"))
    )
    (net (code "203") (name "Net-(U4-A2)") (class "Default")
      (node (ref "R20") (pin "1") (pintype "passive"))
      (node (ref "U4") (pin "4") (pinfunction "A2_4") (pintype "passive"))
    )
    (net (code "204") (name "Net-(U5-DACA)") (class "Default")
      (node (ref "R1") (pin "2") (pintype "passive"))
      (node (ref "U5") (pin "12") (pinfunction "DACA_12") (pintype "passive"))
    )
    (net (code "205") (name "Net-(U5-DACB)") (class "Default")
      (node (ref "R2") (pin "2") (pintype "passive"))
      (node (ref "U5") (pin "11") (pinfunction "DACB_11") (pintype "passive"))
    )
    (net (code "206") (name "Net-(U5-DACC)") (class "Default")
      (node (ref "R3") (pin "2") (pintype "passive"))
      (node (ref "U5") (pin "10") (pinfunction "DACC_10") (pintype "passive"))
    )
    (net (code "207") (name "Net-(U5-DACD)") (class "Default")
      (node (ref "R4") (pin "2") (pintype "passive"))
      (node (ref "U5") (pin "9") (pinfunction "DACD_9") (pintype "passive"))
    )
    (net (code "208") (name "PW_VCC") (class "Default")
      (node (ref "D1") (pin "1") (pinfunction "A_1") (pintype "passive"))
      (node (ref "J4") (pin "1") (pinfunction "1_1") (pintype "passive"))
    )
    (net (code "209") (name "VCC3.3_B") (class "Default")
      (node (ref "P36") (pin "32") (pinfunction "32_32") (pintype "passive"))
      (node (ref "P44") (pin "3") (pinfunction "3_3") (pintype "passive"))
      (node (ref "P46") (pin "3") (pinfunction "3_3") (pintype "passive"))
      (node (ref "R100") (pin "2") (pintype "passive"))
      (node (ref "R104") (pin "2") (pintype "passive"))
      (node (ref "R109") (pin "2") (pintype "passive"))
      (node (ref "R11") (pin "2") (pintype "passive"))
      (node (ref "R113") (pin "2") (pintype "passive"))
      (node (ref "R119") (pin "2") (pintype "passive"))
      (node (ref "R12") (pin "2") (pintype "passive"))
      (node (ref "R125") (pin "2") (pintype "passive"))
      (node (ref "R13") (pin "2") (pintype "passive"))
      (node (ref "R130") (pin "2") (pintype "passive"))
      (node (ref "R137") (pin "2") (pintype "passive"))
      (node (ref "R14") (pin "2") (pintype "passive"))
      (node (ref "R141") (pin "2") (pintype "passive"))
      (node (ref "R15") (pin "1") (pintype "passive"))
      (node (ref "R16") (pin "1") (pintype "passive"))
      (node (ref "R17") (pin "2") (pintype "passive"))
      (node (ref "R18") (pin "2") (pintype "passive"))
      (node (ref "R19") (pin "2") (pintype "passive"))
      (node (ref "R20") (pin "2") (pintype "passive"))
      (node (ref "R21") (pin "2") (pintype "passive"))
      (node (ref "R22") (pin "2") (pintype "passive"))
      (node (ref "R23") (pin "1") (pintype "passive"))
      (node (ref "R24") (pin "1") (pintype "passive"))
      (node (ref "R25") (pin "2") (pintype "passive"))
      (node (ref "R26") (pin "2") (pintype "passive"))
      (node (ref "R27") (pin "2") (pintype "passive"))
      (node (ref "R28") (pin "2") (pintype "passive"))
      (node (ref "R30") (pin "2") (pintype "passive"))
      (node (ref "R31") (pin "2") (pintype "passive"))
      (node (ref "R33") (pin "2") (pintype "passive"))
      (node (ref "R34") (pin "2") (pintype "passive"))
      (node (ref "R36") (pin "2") (pintype "passive"))
      (node (ref "R37") (pin "2") (pintype "passive"))
      (node (ref "R38") (pin "2") (pintype "passive"))
      (node (ref "R40") (pin "2") (pintype "passive"))
      (node (ref "R42") (pin "2") (pintype "passive"))
      (node (ref "R43") (pin "2") (pintype "passive"))
      (node (ref "R44") (pin "2") (pintype "passive"))
      (node (ref "R48") (pin "2") (pintype "passive"))
      (node (ref "R49") (pin "2") (pintype "passive"))
      (node (ref "R50") (pin "2") (pintype "passive"))
      (node (ref "R53") (pin "2") (pintype "passive"))
      (node (ref "R54") (pin "2") (pintype "passive"))
      (node (ref "R56") (pin "2") (pintype "passive"))
      (node (ref "R57") (pin "2") (pintype "passive"))
      (node (ref "R58") (pin "2") (pintype "passive"))
      (node (ref "R60") (pin "2") (pintype "passive"))
      (node (ref "R64") (pin "2") (pintype "passive"))
      (node (ref "R65") (pin "2") (pintype "passive"))
      (node (ref "R66") (pin "2") (pintype "passive"))
      (node (ref "R67") (pin "2") (pintype "passive"))
      (node (ref "R68") (pin "2") (pintype "passive"))
      (node (ref "R70") (pin "2") (pintype "passive"))
      (node (ref "R73") (pin "2") (pintype "passive"))
      (node (ref "R74") (pin "2") (pintype "passive"))
      (node (ref "R75") (pin "2") (pintype "passive"))
      (node (ref "R77") (pin "2") (pintype "passive"))
      (node (ref "R78") (pin "2") (pintype "passive"))
      (node (ref "R81") (pin "2") (pintype "passive"))
      (node (ref "R82") (pin "2") (pintype "passive"))
      (node (ref "R83") (pin "2") (pintype "passive"))
      (node (ref "R85") (pin "2") (pintype "passive"))
      (node (ref "R86") (pin "2") (pintype "passive"))
      (node (ref "R88") (pin "2") (pintype "passive"))
      (node (ref "R9") (pin "2") (pintype "passive"))
      (node (ref "R96") (pin "2") (pintype "passive"))
      (node (ref "U5") (pin "2") (pinfunction "REFA_2") (pintype "passive"))
      (node (ref "U5") (pin "3") (pinfunction "REFB_3") (pintype "passive"))
      (node (ref "U5") (pin "4") (pinfunction "REFC_4") (pintype "passive"))
      (node (ref "U5") (pin "5") (pinfunction "REFD_5") (pintype "passive"))
    )
    (net (code "210") (name "VCC5") (class "Default")
      (node (ref "P36") (pin "31") (pinfunction "31_31") (pintype "passive"))
      (node (ref "R10") (pin "2") (pintype "passive"))
      (node (ref "R29") (pin "2") (pintype "passive"))
      (node (ref "R32") (pin "2") (pintype "passive"))
      (node (ref "R35") (pin "2") (pintype "passive"))
      (node (ref "R39") (pin "2") (pintype "passive"))
      (node (ref "R41") (pin "2") (pintype "passive"))
      (node (ref "R45") (pin "2") (pintype "passive"))
      (node (ref "R51") (pin "2") (pintype "passive"))
      (node (ref "R59") (pin "2") (pintype "passive"))
      (node (ref "R61") (pin "2") (pintype "passive"))
      (node (ref "R69") (pin "2") (pintype "passive"))
      (node (ref "R72") (pin "2") (pintype "passive"))
      (node (ref "R76") (pin "2") (pintype "passive"))
      (node (ref "R80") (pin "2") (pintype "passive"))
      (node (ref "R84") (pin "2") (pintype "passive"))
      (node (ref "R87") (pin "2") (pintype "passive"))
      (node (ref "U1") (pin "8") (pinfunction "VCC_8") (pintype "passive"))
      (node (ref "U2") (pin "8") (pinfunction "VCC_8") (pintype "passive"))
      (node (ref "U3") (pin "8") (pinfunction "VCC_8") (pintype "passive"))
      (node (ref "U4") (pin "8") (pinfunction "VCC_8") (pintype "passive"))
      (node (ref "U5") (pin "14") (pinfunction "VDD_14") (pintype "passive"))
    )
    (net (code "211") (name "VCC24_B") (class "Default")
      (node (ref "C2") (pin "1") (pinfunction "VCC_1") (pintype "passive"))
      (node (ref "C3") (pin "1") (pintype "passive"))
      (node (ref "D39") (pin "A") (pinfunction "A_A") (pintype "passive"))
      (node (ref "D40") (pin "A") (pinfunction "A_A") (pintype "passive"))
      (node (ref "D42") (pin "A") (pinfunction "A_A") (pintype "passive"))
      (node (ref "D43") (pin "A") (pinfunction "A_A") (pintype "passive"))
      (node (ref "D44") (pin "2") (pinfunction "K_2") (pintype "passive"))
      (node (ref "D45") (pin "2") (pinfunction "K_2") (pintype "passive"))
      (node (ref "D46") (pin "2") (pinfunction "K_2") (pintype "passive"))
      (node (ref "D47") (pin "2") (pinfunction "K_2") (pintype "passive"))
      (node (ref "D48") (pin "2") (pinfunction "K_2") (pintype "passive"))
      (node (ref "D49") (pin "A") (pinfunction "A_A") (pintype "passive"))
      (node (ref "D50") (pin "2") (pinfunction "K_2") (pintype "passive"))
      (node (ref "D51") (pin "A") (pinfunction "A_A") (pintype "passive"))
      (node (ref "D52") (pin "2") (pinfunction "K_2") (pintype "passive"))
      (node (ref "D53") (pin "2") (pinfunction "K_2") (pintype "passive"))
      (node (ref "D54") (pin "A") (pinfunction "A_A") (pintype "passive"))
      (node (ref "D55") (pin "2") (pinfunction "K_2") (pintype "passive"))
      (node (ref "D56") (pin "2") (pinfunction "K_2") (pintype "passive"))
      (node (ref "D57") (pin "A") (pinfunction "A_A") (pintype "passive"))
      (node (ref "D58") (pin "A") (pinfunction "A_A") (pintype "passive"))
      (node (ref "D59") (pin "A") (pinfunction "A_A") (pintype "passive"))
      (node (ref "F1") (pin "2") (pinfunction "2_2") (pintype "passive"))
      (node (ref "P1") (pin "1") (pinfunction "1_1") (pintype "passive"))
      (node (ref "P2") (pin "1") (pinfunction "1_1") (pintype "passive"))
      (node (ref "P36") (pin "1") (pinfunction "1_1") (pintype "passive"))
      (node (ref "P38") (pin "1") (pinfunction "1_1") (pintype "passive"))
      (node (ref "P4") (pin "1") (pinfunction "1_1") (pintype "passive"))
      (node (ref "P48") (pin "1") (pinfunction "1_1") (pintype "passive"))
      (node (ref "P53") (pin "1") (pinfunction "1_1") (pintype "passive"))
      (node (ref "P60") (pin "1") (pinfunction "1_1") (pintype "passive"))
      (node (ref "P61") (pin "1") (pinfunction "1_1") (pintype "passive"))
      (node (ref "P62") (pin "1") (pinfunction "1_1") (pintype "passive"))
      (node (ref "R106") (pin "1") (pinfunction "1_1") (pintype "passive"))
      (node (ref "R46") (pin "2") (pintype "passive"))
      (node (ref "R47") (pin "2") (pintype "passive"))
      (node (ref "R5") (pin "1") (pintype "passive"))
      (node (ref "R52") (pin "2") (pintype "passive"))
      (node (ref "R55") (pin "2") (pintype "passive"))
      (node (ref "R6") (pin "2") (pintype "passive"))
      (node (ref "R62") (pin "2") (pintype "passive"))
      (node (ref "R63") (pin "2") (pintype "passive"))
      (node (ref "R7") (pin "1") (pintype "passive"))
      (node (ref "R71") (pin "2") (pintype "passive"))
      (node (ref "R79") (pin "2") (pintype "passive"))
      (node (ref "R8") (pin "2") (pintype "passive"))
    )
  )
)
